# Optical_Compressor_V2.net
KiCad netlist of a schematic drawn in Altium Designer
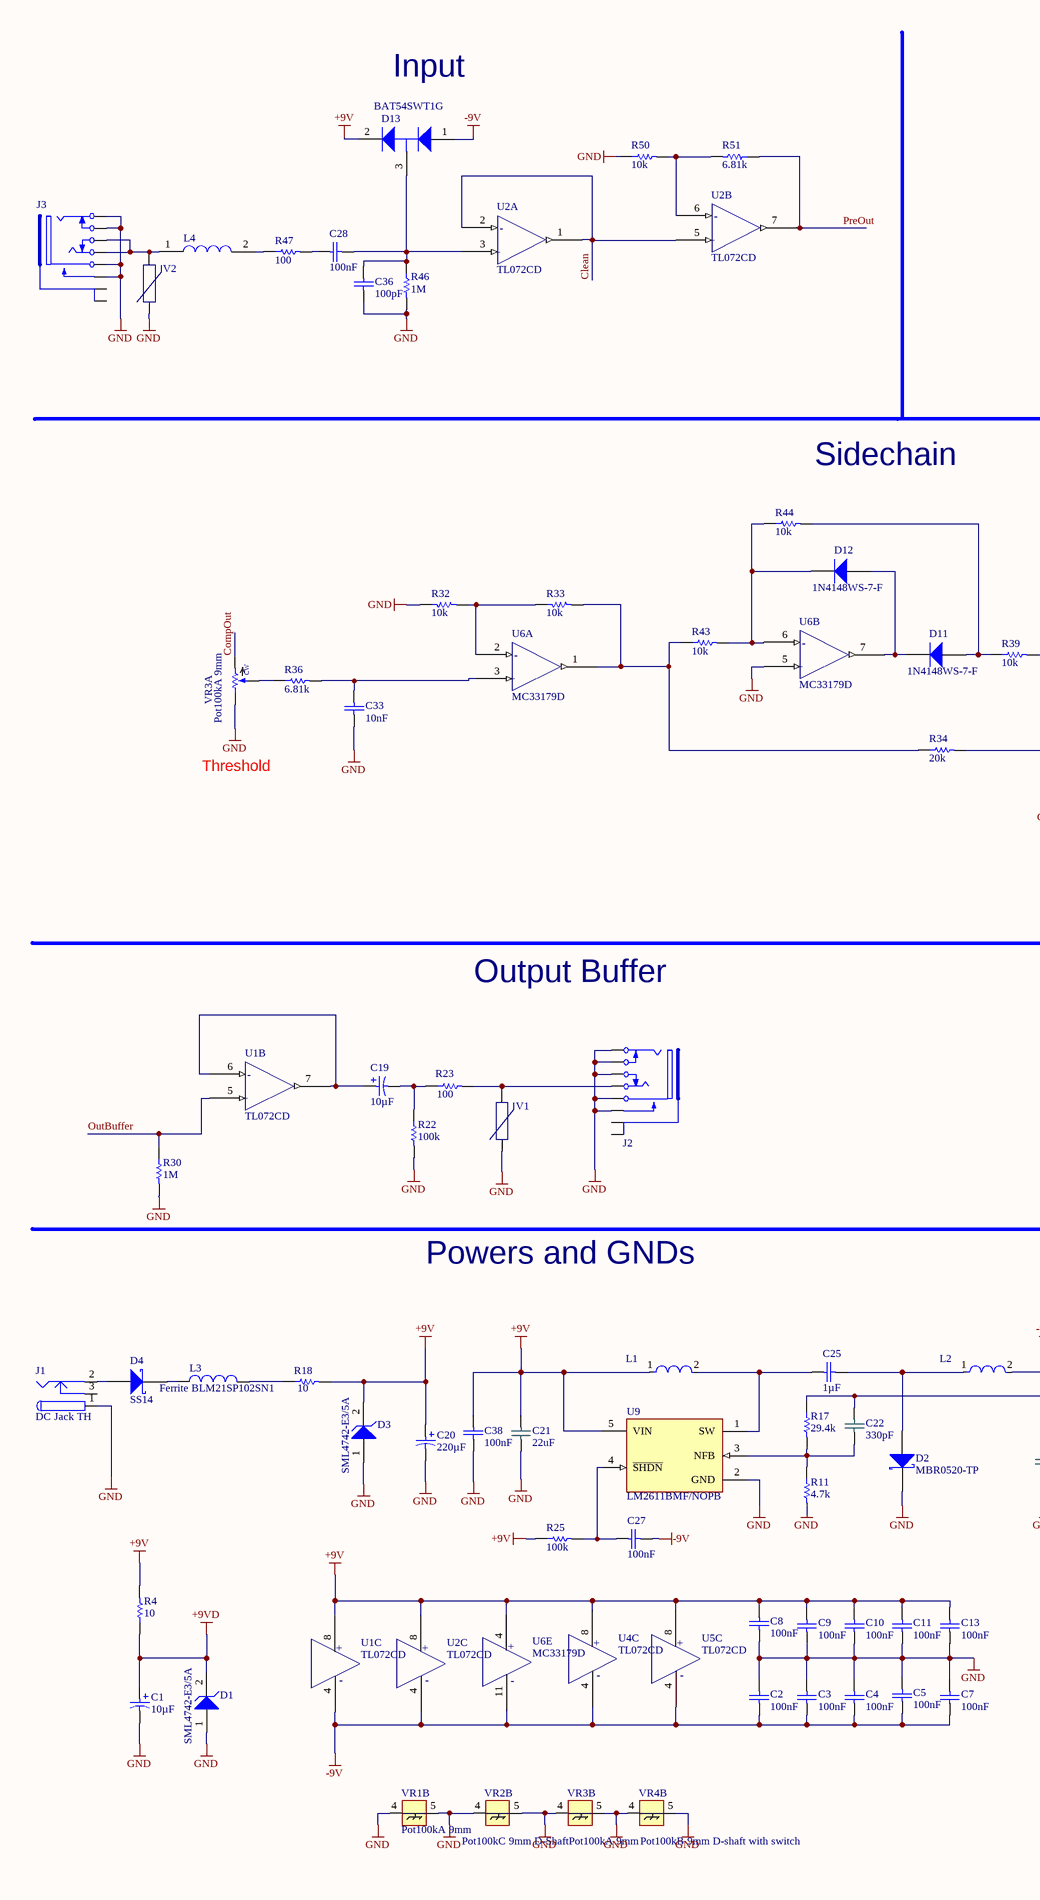
[diagram p0: Optical Compressor V2.SchDoc, left]
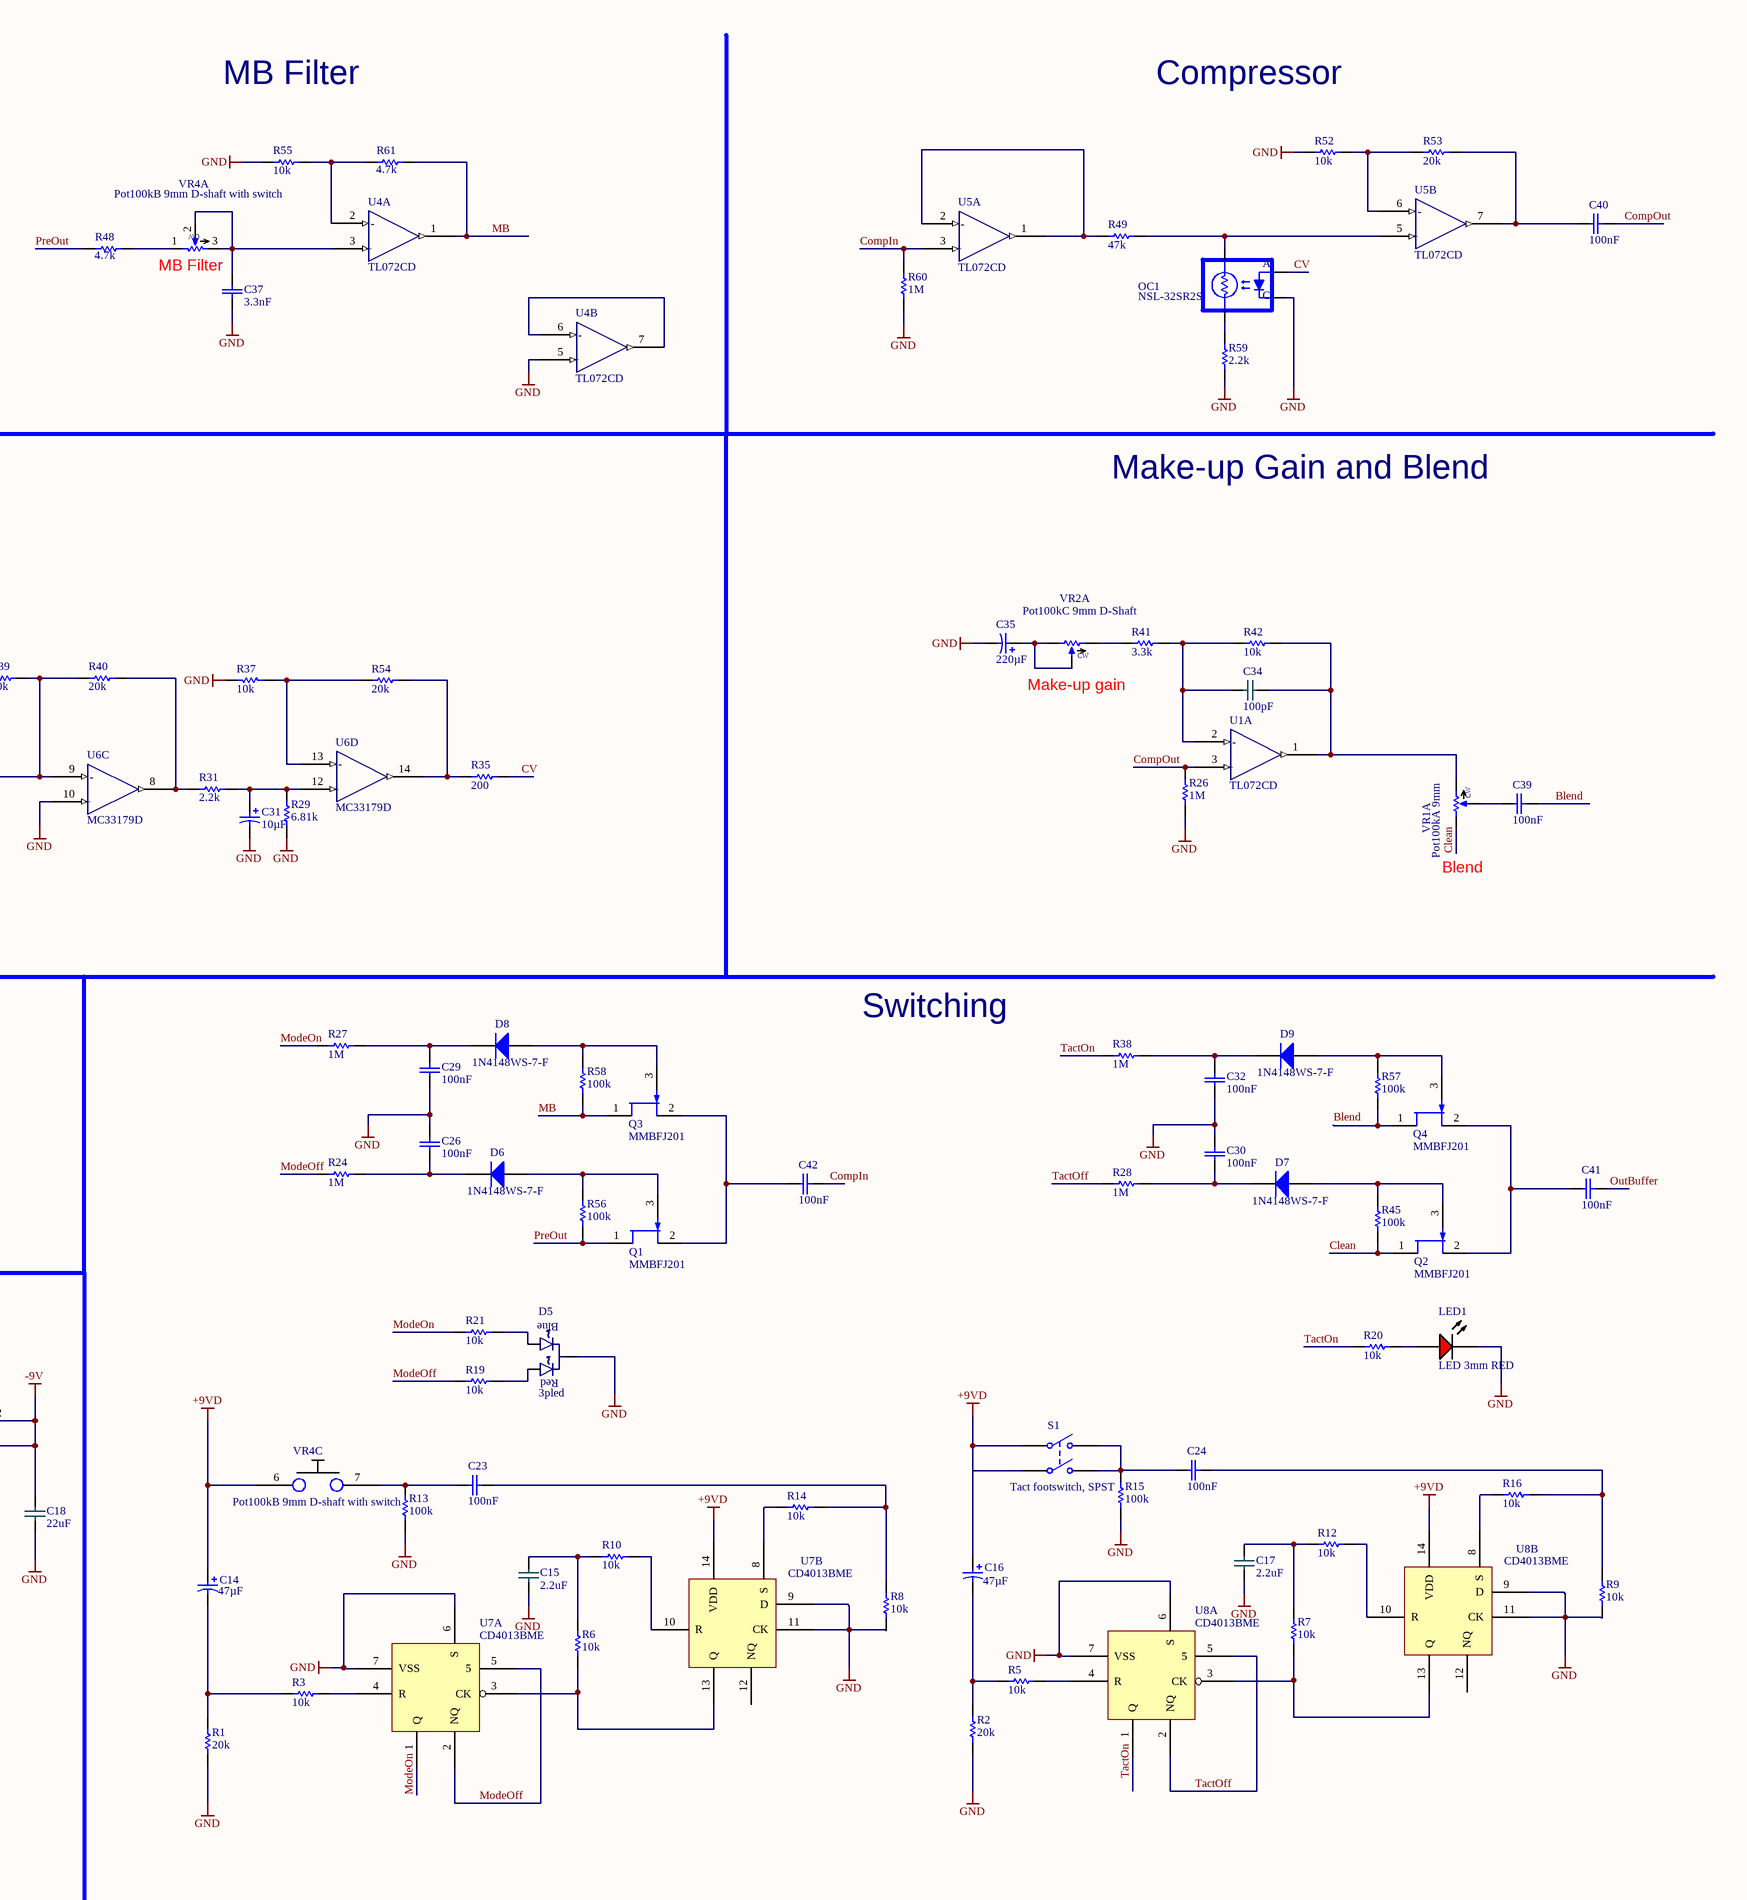
[diagram p1: Optical Compressor V2.SchDoc, right]

(export (version "E")
  (design (tool "Eeschema 10.0.6"))
  (components
    (comp (ref "C1")
      (value "Cap pol 10µF 35V")
      (footprint "E-CAP, SMT, diameter 5mm, height 5.4mm")
      (description "Cap Aluminum 10uF 35V ±20% (5x5.4mm) SMD 2000h 85°C")
      (fields (field (name "CAPACITANCE") "10µF"))
      (libsource (lib "Darkglass Electronics") (part "Capacitor Polarized"))
    )
    (comp (ref "C2")
      (value "Cap 100nF 0603 X7R")
      (footprint "0603-CAP")
      (description "Cap 100nF 0603 X7R 50V +-10%")
      (fields (field (name "CAPACITANCE") "100nF"))
      (libsource (lib "Darkglass Electronics") (part "Capacitor Non-polarized"))
    )
    (comp (ref "C3")
      (value "Cap 100nF 0603 X7R")
      (footprint "0603-CAP")
      (description "Cap 100nF 0603 X7R 50V +-10%")
      (fields (field (name "CAPACITANCE") "100nF"))
      (libsource (lib "Darkglass Electronics") (part "Capacitor Non-polarized"))
    )
    (comp (ref "C4")
      (value "Cap 100nF 0603 X7R")
      (footprint "0603-CAP")
      (description "Cap 100nF 0603 X7R 50V +-10%")
      (fields (field (name "CAPACITANCE") "100nF"))
      (libsource (lib "Darkglass Electronics") (part "Capacitor Non-polarized"))
    )
    (comp (ref "C5")
      (value "Cap 100nF 0603 X7R")
      (footprint "0603-CAP")
      (description "Cap 100nF 0603 X7R 50V +-10%")
      (fields (field (name "CAPACITANCE") "100nF"))
      (libsource (lib "Darkglass Electronics") (part "Capacitor Non-polarized"))
    )
    (comp (ref "C7")
      (value "Cap 100nF 0603 X7R")
      (footprint "0603-CAP")
      (description "Cap 100nF 0603 X7R 50V +-10%")
      (fields (field (name "CAPACITANCE") "100nF"))
      (libsource (lib "Darkglass Electronics") (part "Capacitor Non-polarized"))
    )
    (comp (ref "C8")
      (value "Cap 100nF 0603 X7R")
      (footprint "0603-CAP")
      (description "Cap 100nF 0603 X7R 50V +-10%")
      (fields (field (name "CAPACITANCE") "100nF"))
      (libsource (lib "Darkglass Electronics") (part "Capacitor Non-polarized"))
    )
    (comp (ref "C9")
      (value "Cap 100nF 0603 X7R")
      (footprint "0603-CAP")
      (description "Cap 100nF 0603 X7R 50V +-10%")
      (fields (field (name "CAPACITANCE") "100nF"))
      (libsource (lib "Darkglass Electronics") (part "Capacitor Non-polarized"))
    )
    (comp (ref "C10")
      (value "Cap 100nF 0603 X7R")
      (footprint "0603-CAP")
      (description "Cap 100nF 0603 X7R 50V +-10%")
      (fields (field (name "CAPACITANCE") "100nF"))
      (libsource (lib "Darkglass Electronics") (part "Capacitor Non-polarized"))
    )
    (comp (ref "C11")
      (value "Cap 100nF 0603 X7R")
      (footprint "0603-CAP")
      (description "Cap 100nF 0603 X7R 50V +-10%")
      (fields (field (name "CAPACITANCE") "100nF"))
      (libsource (lib "Darkglass Electronics") (part "Capacitor Non-polarized"))
    )
    (comp (ref "C13")
      (value "Cap 100nF 0603 X7R")
      (footprint "0603-CAP")
      (description "Cap 100nF 0603 X7R 50V +-10%")
      (fields (field (name "CAPACITANCE") "100nF"))
      (libsource (lib "Darkglass Electronics") (part "Capacitor Non-polarized"))
    )
    (comp (ref "C14")
      (value "Cap pol 47µF 16V")
      (footprint "E-CAP, SMT, diameter 6.3mm, height 5.4mm")
      (description "Cap Aluminum 47uF 16V ±20% (6.3x5.4mm) SMD 2000h 85°C")
      (fields (field (name "CAPACITANCE") "47µF"))
      (libsource (lib "Darkglass Electronics") (part "Capacitor Polarized"))
    )
    (comp (ref "C15")
      (value "Cap 0805 2.2uF")
      (footprint "0805-CAP")
      (description "2.2uF, 25V, X5R, 20%")
      (fields (field (name "TOLERANCE") "20%") (field (name "CAPACITANCE") "2.2uF"))
      (libsource (lib "Darkglass Electronics") (part "Capacitor NP"))
    )
    (comp (ref "C16")
      (value "Cap pol 47µF 16V")
      (footprint "E-CAP, SMT, diameter 6.3mm, height 5.4mm")
      (description "Cap Aluminum 47uF 16V ±20% (6.3x5.4mm) SMD 2000h 85°C")
      (fields (field (name "CAPACITANCE") "47µF"))
      (libsource (lib "Darkglass Electronics") (part "Capacitor Polarized"))
    )
    (comp (ref "C17")
      (value "Cap 0805 2.2uF")
      (footprint "0805-CAP")
      (description "2.2uF, 25V, X5R, 20%")
      (fields (field (name "TOLERANCE") "20%") (field (name "CAPACITANCE") "2.2uF"))
      (libsource (lib "Darkglass Electronics") (part "Capacitor NP"))
    )
    (comp (ref "C18")
      (value "22uF")
      (footprint "0805-CAP")
      (description "22uF, 16V, X5R, 20%")
      (fields
        (field (name "TOLERANCE") "20%")
        (field (name "VOLTAGE") "16V")
        (field (name "PUBLISHER") "Altium Limited")
      )
      (libsource (lib "Darkglass Electronics") (part "=Capacitance"))
    )
    (comp (ref "C19")
      (value "Cap pol 10µF 35V")
      (footprint "E-CAP, SMT, diameter 5mm, height 5.4mm")
      (description "Cap Aluminum 10uF 35V ±20% (5x5.4mm) SMD 2000h 85°C")
      (fields (field (name "CAPACITANCE") "10µF"))
      (libsource (lib "Darkglass Electronics") (part "Capacitor Polarized"))
    )
    (comp (ref "C20")
      (value "Cap pol 220µF 16V")
      (footprint "E-CAP, SMT, diameter 6.3mm, height 7.7mm")
      (description "Cap Aluminum 220uF 16V ±20% (6.3x7.7mm) SMD 2000h 85°C")
      (fields (field (name "CAPACITANCE") "220µF"))
      (libsource (lib "Darkglass Electronics") (part "Capacitor Polarized"))
    )
    (comp (ref "C21")
      (value "22uF")
      (footprint "0805-CAP")
      (description "22uF, 16V, X5R, 20%")
      (fields
        (field (name "TOLERANCE") "20%")
        (field (name "VOLTAGE") "16V")
        (field (name "PUBLISHER") "Altium Limited")
      )
      (libsource (lib "Darkglass Electronics") (part "=Capacitance"))
    )
    (comp (ref "C22")
      (value "330pF")
      (footprint "0603-CAP")
      (description "330pF,  5%,  50V,  C0G")
      (fields (field (name "TOLERANCE") "5%") (field (name "VOLTAGE") "50V"))
      (libsource (lib "Darkglass Electronics") (part "Capacitor NP"))
    )
    (comp (ref "C23")
      (value "Cap 100nF 0603 X7R")
      (footprint "0603-CAP")
      (description "Cap 100nF 0603 X7R 50V +-10%")
      (fields (field (name "CAPACITANCE") "100nF"))
      (libsource (lib "Darkglass Electronics") (part "Capacitor Non-polarized"))
    )
    (comp (ref "C24")
      (value "Cap 100nF 0603 X7R")
      (footprint "0603-CAP")
      (description "Cap 100nF 0603 X7R 50V +-10%")
      (fields (field (name "CAPACITANCE") "100nF"))
      (libsource (lib "Darkglass Electronics") (part "Capacitor Non-polarized"))
    )
    (comp (ref "C25")
      (value "Cap 1µF 0805 X7R")
      (footprint "0805-CAP")
      (description "Cap 1µF 0805 X7R 50V +-10%")
      (fields (field (name "CAPACITANCE") "1µF"))
      (libsource (lib "Darkglass Electronics") (part "Capacitor Non-polarized"))
    )
    (comp (ref "C26")
      (value "Cap 100nF 0603 X7R")
      (footprint "0603-CAP")
      (description "Cap 100nF 0603 X7R 50V +-10%")
      (fields (field (name "CAPACITANCE") "100nF"))
      (libsource (lib "Darkglass Electronics") (part "Capacitor Non-polarized"))
    )
    (comp (ref "C27")
      (value "Cap 100nF 0603 X7R")
      (footprint "0603-CAP")
      (description "Cap 100nF 0603 X7R 50V +-10%")
      (fields (field (name "CAPACITANCE") "100nF"))
      (libsource (lib "Darkglass Electronics") (part "Capacitor Non-polarized"))
    )
    (comp (ref "C28")
      (value "Cap 100nF 1206 C0G")
      (footprint "1206-CAP")
      (description "Cap 100nF 1206 C0G 50V +-5%")
      (fields (field (name "CAPACITANCE") "100nF"))
      (libsource (lib "Darkglass Electronics") (part "Capacitor Non-polarized"))
    )
    (comp (ref "C29")
      (value "Cap 100nF 0603 X7R")
      (footprint "0603-CAP")
      (description "Cap 100nF 0603 X7R 50V +-10%")
      (fields (field (name "CAPACITANCE") "100nF"))
      (libsource (lib "Darkglass Electronics") (part "Capacitor Non-polarized"))
    )
    (comp (ref "C30")
      (value "Cap 100nF 0603 X7R")
      (footprint "0603-CAP")
      (description "Cap 100nF 0603 X7R 50V +-10%")
      (fields (field (name "CAPACITANCE") "100nF"))
      (libsource (lib "Darkglass Electronics") (part "Capacitor Non-polarized"))
    )
    (comp (ref "C31")
      (value "Cap pol 10µF 35V")
      (footprint "E-CAP, SMT, diameter 5mm, height 5.4mm")
      (description "Cap Aluminum 10uF 35V ±20% (5x5.4mm) SMD 2000h 85°C")
      (fields (field (name "CAPACITANCE") "10µF"))
      (libsource (lib "Darkglass Electronics") (part "Capacitor Polarized"))
    )
    (comp (ref "C32")
      (value "Cap 100nF 0603 X7R")
      (footprint "0603-CAP")
      (description "Cap 100nF 0603 X7R 50V +-10%")
      (fields (field (name "CAPACITANCE") "100nF"))
      (libsource (lib "Darkglass Electronics") (part "Capacitor Non-polarized"))
    )
    (comp (ref "C33")
      (value "Cap 10nF 0603 C0G")
      (footprint "0603-CAP")
      (description "Cap 10nF 0603 C0G 50V +-5%")
      (fields (field (name "CAPACITANCE") "10nF"))
      (libsource (lib "Darkglass Electronics") (part "Capacitor Non-polarized"))
    )
    (comp (ref "C34")
      (value "Cap 0603 100pF")
      (footprint "0603-CAP")
      (description "100pF, 50V, COG,  5%")
      (fields
        (field (name "CAPACITANCE") "100pF")
        (field (name "TOLERANCE") "5%")
        (field (name "PUBLISHER") "Altium Limited")
      )
      (libsource (lib "Darkglass Electronics") (part "Capacitor NP"))
    )
    (comp (ref "C35")
      (value "Cap pol 220µF 16V")
      (footprint "E-CAP, SMT, diameter 6.3mm, height 7.7mm")
      (description "Cap Aluminum 220uF 16V ±20% (6.3x7.7mm) SMD 2000h 85°C")
      (fields (field (name "CAPACITANCE") "220µF"))
      (libsource (lib "Darkglass Electronics") (part "Capacitor Polarized"))
    )
    (comp (ref "C36")
      (value "Cap 100pF 0603 C0G")
      (footprint "0603-CAP")
      (description "Cap 100pF 0603 C0G 50V +-5%")
      (fields (field (name "CAPACITANCE") "100pF"))
      (libsource (lib "Darkglass Electronics") (part "Capacitor Non-polarized"))
    )
    (comp (ref "C37")
      (value "Cap 3.3nF 0603 C0G")
      (footprint "0603-CAP")
      (description "Cap 3.3nF 0603 C0G 50V +-5%")
      (fields (field (name "CAPACITANCE") "3.3nF"))
      (libsource (lib "Darkglass Electronics") (part "Capacitor Non-polarized"))
    )
    (comp (ref "C38")
      (value "Cap 100nF 0603 X7R")
      (footprint "0603-CAP")
      (description "Cap 100nF 0603 X7R 50V +-10%")
      (fields (field (name "CAPACITANCE") "100nF"))
      (libsource (lib "Darkglass Electronics") (part "Capacitor Non-polarized"))
    )
    (comp (ref "C39")
      (value "Cap 100nF 1206 C0G")
      (footprint "1206-CAP")
      (description "Cap 100nF 1206 C0G 50V +-5%")
      (fields (field (name "CAPACITANCE") "100nF"))
      (libsource (lib "Darkglass Electronics") (part "Capacitor Non-polarized"))
    )
    (comp (ref "C40")
      (value "Cap 100nF 1206 C0G")
      (footprint "1206-CAP")
      (description "Cap 100nF 1206 C0G 50V +-5%")
      (fields (field (name "CAPACITANCE") "100nF"))
      (libsource (lib "Darkglass Electronics") (part "Capacitor Non-polarized"))
    )
    (comp (ref "C41")
      (value "Cap 100nF 1206 C0G")
      (footprint "1206-CAP")
      (description "Cap 100nF 1206 C0G 50V +-5%")
      (fields (field (name "CAPACITANCE") "100nF"))
      (libsource (lib "Darkglass Electronics") (part "Capacitor Non-polarized"))
    )
    (comp (ref "C42")
      (value "Cap 100nF 1206 C0G")
      (footprint "1206-CAP")
      (description "Cap 100nF 1206 C0G 50V +-5%")
      (fields (field (name "CAPACITANCE") "100nF"))
      (libsource (lib "Darkglass Electronics") (part "Capacitor Non-polarized"))
    )
    (comp (ref "D1")
      (value "SML4742-E3/5A")
      (footprint "DO-214AC")
      (description "12V Zener")
      (fields (field (name "TOLERANCE") "10%") (field (name "MANUFACTURER") "Vishay Semiconductors"))
      (libsource (lib "") (part "Symbol_3"))
    )
    (comp (ref "D2")
      (value "MBR0520-TP")
      (footprint "SODFL370X135-2N")
      (description "Rectifier Diode, Schottky, 1 Phase, 1 Element, 0.5A, 20V V(RRM), Silicon")
      (libsource (lib "Darkglass Electronics") (part "SS14"))
    )
    (comp (ref "D3")
      (value "SML4742-E3/5A")
      (footprint "DO-214AC")
      (description "12V Zener")
      (fields (field (name "TOLERANCE") "10%") (field (name "MANUFACTURER") "Vishay Semiconductors"))
      (libsource (lib "") (part "Symbol_3"))
    )
    (comp (ref "D4")
      (value "SS14")
      (footprint "SS14")
      (description "ON SEMICONDUCTOR - SS14 - DIODE, SCHOTTKY, 1A, 40V, DO-214AC-2")
      (fields (field (name "MANUFACTURER") "ON Semiconductor / Fairchild") (field (name "VOLTAGE") "40V"))
      (libsource (lib "") (part "SS14_1"))
    )
    (comp (ref "D5")
      (value "3pled")
      (footprint "LED DUAL REDBLUE")
      (description "3pin led red/blue")
      (fields
        (field (name "MANUFACTURER PART NUMBER") "OSRBMC3131A")
        (field (name "MANUFACTURER") "OptoSupply")
      )
      (libsource (lib "Darkglass Electronics") (part "3pled"))
    )
    (comp (ref "D6")
      (value "1N4148WS-7-F")
      (footprint "1N4148WS-7-F")
      (description "Fast Switching Diode, 75 V, 0.3 A, -65 to 150 degC, 2-Pin SOD323, RoHS, Tape and Reel")
      (fields
        (field (name "VOLTAGE") "75V")
        (field (name "MANUFACTURER") "Pericom")
        (field (name "AVAILABLE PREVIEW IMAGES") "2D")
      )
      (libsource (lib "") (part "Symbol_2"))
    )
    (comp (ref "D7")
      (value "1N4148WS-7-F")
      (footprint "1N4148WS-7-F")
      (description "Fast Switching Diode, 75 V, 0.3 A, -65 to 150 degC, 2-Pin SOD323, RoHS, Tape and Reel")
      (fields
        (field (name "VOLTAGE") "75V")
        (field (name "MANUFACTURER") "Pericom")
        (field (name "AVAILABLE PREVIEW IMAGES") "2D")
      )
      (libsource (lib "") (part "Symbol_2"))
    )
    (comp (ref "D8")
      (value "1N4148WS-7-F")
      (footprint "1N4148WS-7-F")
      (description "Fast Switching Diode, 75 V, 0.3 A, -65 to 150 degC, 2-Pin SOD323, RoHS, Tape and Reel")
      (fields
        (field (name "VOLTAGE") "75V")
        (field (name "MANUFACTURER") "Pericom")
        (field (name "AVAILABLE PREVIEW IMAGES") "2D")
      )
      (libsource (lib "") (part "Symbol_2"))
    )
    (comp (ref "D9")
      (value "1N4148WS-7-F")
      (footprint "1N4148WS-7-F")
      (description "Fast Switching Diode, 75 V, 0.3 A, -65 to 150 degC, 2-Pin SOD323, RoHS, Tape and Reel")
      (fields
        (field (name "VOLTAGE") "75V")
        (field (name "MANUFACTURER") "Pericom")
        (field (name "AVAILABLE PREVIEW IMAGES") "2D")
      )
      (libsource (lib "") (part "Symbol_2"))
    )
    (comp (ref "D11")
      (value "1N4148WS-7-F")
      (footprint "1N4148WS-7-F")
      (description "Fast Switching Diode, 75 V, 0.3 A, -65 to 150 degC, 2-Pin SOD323, RoHS, Tape and Reel")
      (fields
        (field (name "VOLTAGE") "75V")
        (field (name "MANUFACTURER") "Pericom")
        (field (name "AVAILABLE PREVIEW IMAGES") "2D")
      )
      (libsource (lib "") (part "Symbol_2"))
    )
    (comp (ref "D12")
      (value "1N4148WS-7-F")
      (footprint "1N4148WS-7-F")
      (description "Fast Switching Diode, 75 V, 0.3 A, -65 to 150 degC, 2-Pin SOD323, RoHS, Tape and Reel")
      (fields
        (field (name "VOLTAGE") "75V")
        (field (name "MANUFACTURER") "Pericom")
        (field (name "AVAILABLE PREVIEW IMAGES") "2D")
      )
      (libsource (lib "") (part "Symbol_2"))
    )
    (comp (ref "D13")
      (value "BAT54SWT1G")
      (footprint "ONSC-SOT-323-3-419-04_V")
      (description "Rectifier Diode, Schottky, 2 Element, 0.2A, 30V V(RRM), Silicon")
      (libsource (lib "Darkglass Electronics") (part "ONSC-D-A1K2C3-3"))
    )
    (comp (ref "J1")
      (value "DC Jack TH")
      (footprint "DC_Jack")
      (description "Low Voltage Power Supply Connector")
      (fields (field (name "DARKGLASS PART") "D00-0019"))
      (libsource (lib "") (part "Symbol_8"))
    )
    (comp (ref "J2")
      (value "Neutrik TRS Jack with metal nut")
      (footprint "Neutrik Jack with Cliff EMI screen")
      (fields (field (name "DARKGLASS PART") "D00-0011"))
      (libsource (lib "Darkglass Electronics") (part "Neutrik TRS Jack with metal nut"))
    )
    (comp (ref "J3")
      (value "Neutrik TRS Jack with metal nut")
      (footprint "Neutrik Jack with Cliff EMI screen")
      (fields (field (name "DARKGLASS PART") "D00-0011"))
      (libsource (lib "Darkglass Electronics") (part "Neutrik TRS Jack with metal nut"))
    )
    (comp (ref "L1")
      (value "CR32NP-100KC")
      (footprint "INDC3340X27N")
      (description "General Purpose Inductor, 10uH, 10%, 1 Element, Ferrite-Core, SMD, 1514")
      (fields (field (name "TOLERANCE") "10%"))
      (libsource (lib "Darkglass Electronics") (part "725321dda6339637d4d059423bc1c3c"))
    )
    (comp (ref "L2")
      (value "CR32NP-100KC")
      (footprint "INDC3340X27N")
      (description "General Purpose Inductor, 10uH, 10%, 1 Element, Ferrite-Core, SMD, 1514")
      (fields (field (name "TOLERANCE") "10%"))
      (libsource (lib "Darkglass Electronics") (part "725321dda6339637d4d059423bc1c3c"))
    )
    (comp (ref "L3")
      (value "Ferrite BLM21SP102SN1")
      (footprint "0805-IND")
      (description "Ferrite Beads Multi-Layer High Current 1KOhm 25% 100MHz 1.6A 0.12Ohm DCR")
      (fields
        (field (name "MANUFACTURER PART NUMBER") "BLM21SP102SN1D")
        (field (name "MANUFACTURER") "Murata")
        (field (name "SOURCE") "jimi.SchLib")
      )
      (libsource (lib "Darkglass Electronics") (part "ferrite 1k 0805"))
    )
    (comp (ref "L4")
      (value "MAF1005GAD352A")
      (footprint "0402 COMPONENT")
      (description "FERRITE BEAD, AUDIO, 500 OHM 0402 Low THD+N")
      (libsource (lib "Darkglass Electronics") (part "Audio 500R 0402"))
    )
    (comp (ref "LED1")
      (value "LED 3mm RED")
      (footprint "KING-WP710A10QBCD_V")
      (description "THT LED round mono-color waterclear, WL-TMRW , RED")
      (fields
        (field (name "DARKGLASS PART") "D00-0042")
        (field (name "MANUFACTURER") "Wuerth Elektronik")
        (field (name "AVAILABLE PREVIEW IMAGES") "2D")
      )
      (libsource (lib "Darkglass Electronics") (part "LED 3mm RED"))
    )
    (comp (ref "OC1")
      (value "NSL-32SR2S")
      (footprint "NSL")
      (description "Optoisolator Photocell Optocoupler 1 Channel")
      (fields (field (name "MF") "Advanced Photonix"))
      (libsource (lib "SnapEDAsch") (part "NSL-32SR2S"))
    )
    (comp (ref "Q1")
      (value "MMBFJ201")
      (footprint "MMBFJ201")
      (description "JFET N-CH 40V 350MW SOT23")
      (fields
        (field (name "MOUSER PART") "512-MMBFJ201")
        (field (name "MANUFACTURER") "ON Semiconductor / Fairchild")
      )
      (libsource (lib "") (part "Symbol_1"))
    )
    (comp (ref "Q2")
      (value "MMBFJ201")
      (footprint "MMBFJ201")
      (description "JFET N-CH 40V 350MW SOT23")
      (fields
        (field (name "MOUSER PART") "512-MMBFJ201")
        (field (name "MANUFACTURER") "ON Semiconductor / Fairchild")
      )
      (libsource (lib "") (part "Symbol_1"))
    )
    (comp (ref "Q3")
      (value "MMBFJ201")
      (footprint "MMBFJ201")
      (description "JFET N-CH 40V 350MW SOT23")
      (fields
        (field (name "MOUSER PART") "512-MMBFJ201")
        (field (name "MANUFACTURER") "ON Semiconductor / Fairchild")
      )
      (libsource (lib "") (part "Symbol_1"))
    )
    (comp (ref "Q4")
      (value "MMBFJ201")
      (footprint "MMBFJ201")
      (description "JFET N-CH 40V 350MW SOT23")
      (fields
        (field (name "MOUSER PART") "512-MMBFJ201")
        (field (name "MANUFACTURER") "ON Semiconductor / Fairchild")
      )
      (libsource (lib "") (part "Symbol_1"))
    )
    (comp (ref "R1")
      (value "Res 20k 1% 0603")
      (footprint "0603-RES")
      (description "Resistor 20k +-1% 0603 Thin film 0.1W +-50ppm/°C")
      (fields (field (name "RESISTANCE") "20k") (field (name "POWER") "100mW"))
      (libsource (lib "Darkglass Electronics") (part "Resistor"))
    )
    (comp (ref "R2")
      (value "Res 20k 1% 0603")
      (footprint "0603-RES")
      (description "Resistor 20k +-1% 0603 Thin film 0.1W +-50ppm/°C")
      (fields (field (name "RESISTANCE") "20k") (field (name "POWER") "100mW"))
      (libsource (lib "Darkglass Electronics") (part "Resistor"))
    )
    (comp (ref "R3")
      (value "Res 10k 1% 0603")
      (footprint "0603-RES")
      (description "Resistor 10k +-1% 0603 Thick film 0.1W +- 100ppm/°C")
      (fields (field (name "RESISTANCE") "10k") (field (name "POWER") "100mW"))
      (libsource (lib "Darkglass Electronics") (part "Resistor"))
    )
    (comp (ref "R4")
      (value "Res 10R 5% 0805")
      (footprint "0805-RES")
      (description "Resistor 10R +-5% 0805 Thick film 0.125W +-200ppm/°C")
      (fields (field (name "POWER") "125mW") (field (name "RESISTANCE") "10"))
      (libsource (lib "Darkglass Electronics") (part "Resistor"))
    )
    (comp (ref "R5")
      (value "Res 10k 1% 0603")
      (footprint "0603-RES")
      (description "Resistor 10k +-1% 0603 Thick film 0.1W +- 100ppm/°C")
      (fields (field (name "RESISTANCE") "10k") (field (name "POWER") "100mW"))
      (libsource (lib "Darkglass Electronics") (part "Resistor"))
    )
    (comp (ref "R6")
      (value "Res 10k 1% 0603")
      (footprint "0603-RES")
      (description "Resistor 10k +-1% 0603 Thick film 0.1W +- 100ppm/°C")
      (fields (field (name "RESISTANCE") "10k") (field (name "POWER") "100mW"))
      (libsource (lib "Darkglass Electronics") (part "Resistor"))
    )
    (comp (ref "R7")
      (value "Res 10k 1% 0603")
      (footprint "0603-RES")
      (description "Resistor 10k +-1% 0603 Thick film 0.1W +- 100ppm/°C")
      (fields (field (name "RESISTANCE") "10k") (field (name "POWER") "100mW"))
      (libsource (lib "Darkglass Electronics") (part "Resistor"))
    )
    (comp (ref "R8")
      (value "Res 10k 1% 0603")
      (footprint "0603-RES")
      (description "Resistor 10k +-1% 0603 Thick film 0.1W +- 100ppm/°C")
      (fields (field (name "RESISTANCE") "10k") (field (name "POWER") "100mW"))
      (libsource (lib "Darkglass Electronics") (part "Resistor"))
    )
    (comp (ref "R9")
      (value "Res 10k 1% 0603")
      (footprint "0603-RES")
      (description "Resistor 10k +-1% 0603 Thick film 0.1W +- 100ppm/°C")
      (fields (field (name "RESISTANCE") "10k") (field (name "POWER") "100mW"))
      (libsource (lib "Darkglass Electronics") (part "Resistor"))
    )
    (comp (ref "R10")
      (value "Res 10k 1% 0603")
      (footprint "0603-RES")
      (description "Resistor 10k +-1% 0603 Thick film 0.1W +- 100ppm/°C")
      (fields (field (name "RESISTANCE") "10k") (field (name "POWER") "100mW"))
      (libsource (lib "Darkglass Electronics") (part "Resistor"))
    )
    (comp (ref "R11")
      (value "Res 4.7k 1% 0603")
      (footprint "0603-RES")
      (description "Resistor 4.7k +-1% 0603 Thin film 0.1W +-50ppm/°C")
      (fields (field (name "POWER") "100mW") (field (name "RESISTANCE") "4.7k"))
      (libsource (lib "Darkglass Electronics") (part "Resistor"))
    )
    (comp (ref "R12")
      (value "Res 10k 1% 0603")
      (footprint "0603-RES")
      (description "Resistor 10k +-1% 0603 Thick film 0.1W +- 100ppm/°C")
      (fields (field (name "RESISTANCE") "10k") (field (name "POWER") "100mW"))
      (libsource (lib "Darkglass Electronics") (part "Resistor"))
    )
    (comp (ref "R13")
      (value "Res 100k 1% 0603")
      (footprint "0603-RES")
      (description "Resistor 100k +-1% 0603 Thin film 0.1W +-50ppm/°C")
      (fields (field (name "POWER") "100mW") (field (name "RESISTANCE") "100k"))
      (libsource (lib "Darkglass Electronics") (part "Resistor"))
    )
    (comp (ref "R14")
      (value "Res 10k 1% 0603")
      (footprint "0603-RES")
      (description "Resistor 10k +-1% 0603 Thick film 0.1W +- 100ppm/°C")
      (fields (field (name "RESISTANCE") "10k") (field (name "POWER") "100mW"))
      (libsource (lib "Darkglass Electronics") (part "Resistor"))
    )
    (comp (ref "R15")
      (value "Res 100k 1% 0603")
      (footprint "0603-RES")
      (description "Resistor 100k +-1% 0603 Thin film 0.1W +-50ppm/°C")
      (fields (field (name "POWER") "100mW") (field (name "RESISTANCE") "100k"))
      (libsource (lib "Darkglass Electronics") (part "Resistor"))
    )
    (comp (ref "R16")
      (value "Res 10k 1% 0603")
      (footprint "0603-RES")
      (description "Resistor 10k +-1% 0603 Thick film 0.1W +- 100ppm/°C")
      (fields (field (name "RESISTANCE") "10k") (field (name "POWER") "100mW"))
      (libsource (lib "Darkglass Electronics") (part "Resistor"))
    )
    (comp (ref "R17")
      (value "Res 29.4k 1% 0805")
      (footprint "0805-RES")
      (description "Resistor 29.4k +-1% 0805 Thick film 0.125W +- 100ppm/°C")
      (fields (field (name "RESISTANCE") "29.4k") (field (name "POWER") "125mW"))
      (libsource (lib "Darkglass Electronics") (part "Resistor"))
    )
    (comp (ref "R18")
      (value "Res 10R 5% 0805")
      (footprint "0805-RES")
      (description "Resistor 10R +-5% 0805 Thick film 0.125W +-200ppm/°C")
      (fields (field (name "POWER") "125mW") (field (name "RESISTANCE") "10"))
      (libsource (lib "Darkglass Electronics") (part "Resistor"))
    )
    (comp (ref "R19")
      (value "Res 10k 1% 0603")
      (footprint "0603-RES")
      (description "Resistor 10k +-1% 0603 Thick film 0.1W +- 100ppm/°C")
      (fields (field (name "RESISTANCE") "10k") (field (name "POWER") "100mW"))
      (libsource (lib "Darkglass Electronics") (part "Resistor"))
    )
    (comp (ref "R20")
      (value "Res 10k 1% 0603")
      (footprint "0603-RES")
      (description "Resistor 10k +-1% 0603 Thick film 0.1W +- 100ppm/°C")
      (fields (field (name "RESISTANCE") "10k") (field (name "POWER") "100mW"))
      (libsource (lib "Darkglass Electronics") (part "Resistor"))
    )
    (comp (ref "R21")
      (value "Res 10k 1% 0603")
      (footprint "0603-RES")
      (description "Resistor 10k +-1% 0603 Thick film 0.1W +- 100ppm/°C")
      (fields (field (name "RESISTANCE") "10k") (field (name "POWER") "100mW"))
      (libsource (lib "Darkglass Electronics") (part "Resistor"))
    )
    (comp (ref "R22")
      (value "Res 100k 1% 0603")
      (footprint "0603-RES")
      (description "Resistor 100k +-1% 0603 Thin film 0.1W +-50ppm/°C")
      (fields (field (name "POWER") "100mW") (field (name "RESISTANCE") "100k"))
      (libsource (lib "Darkglass Electronics") (part "Resistor"))
    )
    (comp (ref "R23")
      (value "Res 100R 1% 0805")
      (footprint "0805-RES")
      (description "Resistor 100R +-1% 0805 Thin film 0.125W +-50ppm/°C")
      (fields (field (name "POWER") "125mW") (field (name "RESISTANCE") "100"))
      (libsource (lib "Darkglass Electronics") (part "Resistor"))
    )
    (comp (ref "R24")
      (value "Res 1M 1% 0603")
      (footprint "0603-RES")
      (description "Resistor 1M +-1% 0603 Thin film 0.1W +-50ppm/°C")
      (fields (field (name "POWER") "100mW") (field (name "RESISTANCE") "1M"))
      (libsource (lib "Darkglass Electronics") (part "Resistor"))
    )
    (comp (ref "R25")
      (value "Res 100k 1% 0603")
      (footprint "0603-RES")
      (description "Resistor 100k +-1% 0603 Thin film 0.1W +-50ppm/°C")
      (fields (field (name "POWER") "100mW") (field (name "RESISTANCE") "100k"))
      (libsource (lib "Darkglass Electronics") (part "Resistor"))
    )
    (comp (ref "R26")
      (value "Res 1M 1% 0603")
      (footprint "0603-RES")
      (description "Resistor 1M +-1% 0603 Thin film 0.1W +-50ppm/°C")
      (fields (field (name "POWER") "100mW") (field (name "RESISTANCE") "1M"))
      (libsource (lib "Darkglass Electronics") (part "Resistor"))
    )
    (comp (ref "R27")
      (value "Res 1M 1% 0603")
      (footprint "0603-RES")
      (description "Resistor 1M +-1% 0603 Thin film 0.1W +-50ppm/°C")
      (fields (field (name "POWER") "100mW") (field (name "RESISTANCE") "1M"))
      (libsource (lib "Darkglass Electronics") (part "Resistor"))
    )
    (comp (ref "R28")
      (value "Res 1M 1% 0603")
      (footprint "0603-RES")
      (description "Resistor 1M +-1% 0603 Thin film 0.1W +-50ppm/°C")
      (fields (field (name "POWER") "100mW") (field (name "RESISTANCE") "1M"))
      (libsource (lib "Darkglass Electronics") (part "Resistor"))
    )
    (comp (ref "R29")
      (value "Res 6.81k 1% 0603")
      (footprint "0603-RES")
      (description "Resistor 6.81k +-1% 0603 Thin film 0.1W +-50ppm/°C")
      (fields (field (name "POWER") "100mW") (field (name "RESISTANCE") "6.81k"))
      (libsource (lib "Darkglass Electronics") (part "Resistor"))
    )
    (comp (ref "R30")
      (value "Res 1M 1% 0603")
      (footprint "0603-RES")
      (description "Resistor 1M +-1% 0603 Thin film 0.1W +-50ppm/°C")
      (fields (field (name "POWER") "100mW") (field (name "RESISTANCE") "1M"))
      (libsource (lib "Darkglass Electronics") (part "Resistor"))
    )
    (comp (ref "R31")
      (value "Res 2.2k 1% 0603")
      (footprint "0603-RES")
      (description "Resistor 2.2k +-1% 0603 Thin film 0.1W +-50ppm/°C")
      (fields (field (name "POWER") "100mW") (field (name "RESISTANCE") "2.2k"))
      (libsource (lib "Darkglass Electronics") (part "Resistor"))
    )
    (comp (ref "R32")
      (value "Res 10k 1% 0603")
      (footprint "0603-RES")
      (description "Resistor 10k +-1% 0603 Thick film 0.1W +- 100ppm/°C")
      (fields (field (name "RESISTANCE") "10k") (field (name "POWER") "100mW"))
      (libsource (lib "Darkglass Electronics") (part "Resistor"))
    )
    (comp (ref "R33")
      (value "Res 10k 1% 0603")
      (footprint "0603-RES")
      (description "Resistor 10k +-1% 0603 Thick film 0.1W +- 100ppm/°C")
      (fields (field (name "RESISTANCE") "10k") (field (name "POWER") "100mW"))
      (libsource (lib "Darkglass Electronics") (part "Resistor"))
    )
    (comp (ref "R34")
      (value "Res 20k 1% 0603")
      (footprint "0603-RES")
      (description "Resistor 20k +-1% 0603 Thin film 0.1W +-50ppm/°C")
      (fields (field (name "RESISTANCE") "20k") (field (name "POWER") "100mW"))
      (libsource (lib "Darkglass Electronics") (part "Resistor"))
    )
    (comp (ref "R35")
      (value "Res 200R 1% 0805")
      (footprint "0805-RES")
      (description "Resistor 200R +-1% 0805 Thin film 0.125W +-50ppm/°C")
      (fields (field (name "POWER") "125mW") (field (name "RESISTANCE") "200"))
      (libsource (lib "Darkglass Electronics") (part "Resistor"))
    )
    (comp (ref "R36")
      (value "Res 6.81k 1% 0603")
      (footprint "0603-RES")
      (description "Resistor 6.81k +-1% 0603 Thin film 0.1W +-50ppm/°C")
      (fields (field (name "POWER") "100mW") (field (name "RESISTANCE") "6.81k"))
      (libsource (lib "Darkglass Electronics") (part "Resistor"))
    )
    (comp (ref "R37")
      (value "Res 10k 1% 0603")
      (footprint "0603-RES")
      (description "Resistor 10k +-1% 0603 Thick film 0.1W +- 100ppm/°C")
      (fields (field (name "RESISTANCE") "10k") (field (name "POWER") "100mW"))
      (libsource (lib "Darkglass Electronics") (part "Resistor"))
    )
    (comp (ref "R38")
      (value "Res 1M 1% 0603")
      (footprint "0603-RES")
      (description "Resistor 1M +-1% 0603 Thin film 0.1W +-50ppm/°C")
      (fields (field (name "POWER") "100mW") (field (name "RESISTANCE") "1M"))
      (libsource (lib "Darkglass Electronics") (part "Resistor"))
    )
    (comp (ref "R39")
      (value "Res 10k 1% 0603")
      (footprint "0603-RES")
      (description "Resistor 10k +-1% 0603 Thick film 0.1W +- 100ppm/°C")
      (fields (field (name "RESISTANCE") "10k") (field (name "POWER") "100mW"))
      (libsource (lib "Darkglass Electronics") (part "Resistor"))
    )
    (comp (ref "R40")
      (value "Res 20k 1% 0603")
      (footprint "0603-RES")
      (description "Resistor 20k +-1% 0603 Thin film 0.1W +-50ppm/°C")
      (fields (field (name "RESISTANCE") "20k") (field (name "POWER") "100mW"))
      (libsource (lib "Darkglass Electronics") (part "Resistor"))
    )
    (comp (ref "R41")
      (value "Res 3.3k 1% 0603")
      (footprint "0603-RES")
      (description "Resistor 3.3k +-1% 0603 Thin film 0.1W +-50ppm/°C")
      (fields (field (name "POWER") "100mW") (field (name "RESISTANCE") "3.3k"))
      (libsource (lib "Darkglass Electronics") (part "Resistor"))
    )
    (comp (ref "R42")
      (value "Res 10k 1% 0603")
      (footprint "0603-RES")
      (description "Resistor 10k +-1% 0603 Thick film 0.1W +- 100ppm/°C")
      (fields (field (name "RESISTANCE") "10k") (field (name "POWER") "100mW"))
      (libsource (lib "Darkglass Electronics") (part "Resistor"))
    )
    (comp (ref "R43")
      (value "Res 10k 1% 0603")
      (footprint "0603-RES")
      (description "Resistor 10k +-1% 0603 Thick film 0.1W +- 100ppm/°C")
      (fields (field (name "RESISTANCE") "10k") (field (name "POWER") "100mW"))
      (libsource (lib "Darkglass Electronics") (part "Resistor"))
    )
    (comp (ref "R44")
      (value "Res 10k 1% 0603")
      (footprint "0603-RES")
      (description "Resistor 10k +-1% 0603 Thick film 0.1W +- 100ppm/°C")
      (fields (field (name "RESISTANCE") "10k") (field (name "POWER") "100mW"))
      (libsource (lib "Darkglass Electronics") (part "Resistor"))
    )
    (comp (ref "R45")
      (value "Res 100k 1% 0603")
      (footprint "0603-RES")
      (description "Resistor 100k +-1% 0603 Thin film 0.1W +-50ppm/°C")
      (fields (field (name "POWER") "100mW") (field (name "RESISTANCE") "100k"))
      (libsource (lib "Darkglass Electronics") (part "Resistor"))
    )
    (comp (ref "R46")
      (value "Res 1M 1% 0603")
      (footprint "0603-RES")
      (description "Resistor 1M +-1% 0603 Thin film 0.1W +-50ppm/°C")
      (fields (field (name "POWER") "100mW") (field (name "RESISTANCE") "1M"))
      (libsource (lib "Darkglass Electronics") (part "Resistor"))
    )
    (comp (ref "R47")
      (value "Res 100R 1% 0805")
      (footprint "0805-RES")
      (description "Resistor 100R +-1% 0805 Thin film 0.125W +-50ppm/°C")
      (fields (field (name "POWER") "125mW") (field (name "RESISTANCE") "100"))
      (libsource (lib "Darkglass Electronics") (part "Resistor"))
    )
    (comp (ref "R48")
      (value "Res 4.7k 1% 0603")
      (footprint "0603-RES")
      (description "Resistor 4.7k +-1% 0603 Thin film 0.1W +-50ppm/°C")
      (fields (field (name "RESISTANCE") "4.7k") (field (name "POWER") "100mW"))
      (libsource (lib "Darkglass Electronics") (part "Resistor"))
    )
    (comp (ref "R49")
      (value "Res 47k 1% 0603")
      (footprint "0603-RES")
      (description "Resistor 47k +-1% 0603 Thin film 0.1W +-50ppm/°C")
      (fields (field (name "RESISTANCE") "47k") (field (name "POWER") "100mW"))
      (libsource (lib "Darkglass Electronics") (part "Resistor"))
    )
    (comp (ref "R50")
      (value "Res 10k 1% 0603")
      (footprint "0603-RES")
      (description "Resistor 10k +-1% 0603 Thick film 0.1W +- 100ppm/°C")
      (fields (field (name "RESISTANCE") "10k") (field (name "POWER") "100mW"))
      (libsource (lib "Darkglass Electronics") (part "Resistor"))
    )
    (comp (ref "R51")
      (value "Res 6.81k 1% 0603")
      (footprint "0603-RES")
      (description "Resistor 6.81k +-1% 0603 Thin film 0.1W +-50ppm/°C")
      (fields (field (name "POWER") "100mW") (field (name "RESISTANCE") "6.81k"))
      (libsource (lib "Darkglass Electronics") (part "Resistor"))
    )
    (comp (ref "R52")
      (value "Res 10k 1% 0603")
      (footprint "0603-RES")
      (description "Resistor 10k +-1% 0603 Thick film 0.1W +- 100ppm/°C")
      (fields (field (name "RESISTANCE") "10k") (field (name "POWER") "100mW"))
      (libsource (lib "Darkglass Electronics") (part "Resistor"))
    )
    (comp (ref "R53")
      (value "Res 20k 1% 0603")
      (footprint "0603-RES")
      (description "Resistor 20k +-1% 0603 Thin film 0.1W +-50ppm/°C")
      (fields (field (name "RESISTANCE") "20k") (field (name "POWER") "100mW"))
      (libsource (lib "Darkglass Electronics") (part "Resistor"))
    )
    (comp (ref "R54")
      (value "Res 20k 1% 0603")
      (footprint "0603-RES")
      (description "Resistor 20k +-1% 0603 Thin film 0.1W +-50ppm/°C")
      (fields (field (name "RESISTANCE") "20k") (field (name "POWER") "100mW"))
      (libsource (lib "Darkglass Electronics") (part "Resistor"))
    )
    (comp (ref "R55")
      (value "Res 10k 1% 0603")
      (footprint "0603-RES")
      (description "Resistor 10k +-1% 0603 Thick film 0.1W +- 100ppm/°C")
      (fields (field (name "RESISTANCE") "10k") (field (name "POWER") "100mW"))
      (libsource (lib "Darkglass Electronics") (part "Resistor"))
    )
    (comp (ref "R56")
      (value "Res 100k 1% 0603")
      (footprint "0603-RES")
      (description "Resistor 100k +-1% 0603 Thin film 0.1W +-50ppm/°C")
      (fields (field (name "POWER") "100mW") (field (name "RESISTANCE") "100k"))
      (libsource (lib "Darkglass Electronics") (part "Resistor"))
    )
    (comp (ref "R57")
      (value "Res 100k 1% 0603")
      (footprint "0603-RES")
      (description "Resistor 100k +-1% 0603 Thin film 0.1W +-50ppm/°C")
      (fields (field (name "POWER") "100mW") (field (name "RESISTANCE") "100k"))
      (libsource (lib "Darkglass Electronics") (part "Resistor"))
    )
    (comp (ref "R58")
      (value "Res 100k 1% 0603")
      (footprint "0603-RES")
      (description "Resistor 100k +-1% 0603 Thin film 0.1W +-50ppm/°C")
      (fields (field (name "POWER") "100mW") (field (name "RESISTANCE") "100k"))
      (libsource (lib "Darkglass Electronics") (part "Resistor"))
    )
    (comp (ref "R59")
      (value "Res 2.2k 1% 0603")
      (footprint "0603-RES")
      (description "Resistor 2.2k +-1% 0603 Thin film 0.1W +-50ppm/°C")
      (fields (field (name "POWER") "100mW") (field (name "RESISTANCE") "2.2k"))
      (libsource (lib "Darkglass Electronics") (part "Resistor"))
    )
    (comp (ref "R60")
      (value "Res 1M 1% 0603")
      (footprint "0603-RES")
      (description "Resistor 1M +-1% 0603 Thin film 0.1W +-50ppm/°C")
      (fields (field (name "POWER") "100mW") (field (name "RESISTANCE") "1M"))
      (libsource (lib "Darkglass Electronics") (part "Resistor"))
    )
    (comp (ref "R61")
      (value "Res 4.7k 1% 0603")
      (footprint "0603-RES")
      (description "Resistor 4.7k +-1% 0603 Thin film 0.1W +-50ppm/°C")
      (fields (field (name "RESISTANCE") "4.7k") (field (name "POWER") "100mW"))
      (libsource (lib "Darkglass Electronics") (part "Resistor"))
    )
    (comp (ref "S1")
      (value "Tact footswitch, SPST")
      (footprint "Tact-SKHCBEA010")
      (description "Tactile Switches 12x12x4.3mm 130gf")
      (fields
        (field (name "MANUFACTURER PART NUMBER") "SKHCBFA010")
        (field (name "DARKGLASS PART") "D00-0022")
      )
      (libsource (lib "Darkglass Electronics") (part "Tact footswitch"))
    )
    (comp (ref "U1")
      (value "TL072CD")
      (footprint "SOIC8-127P600X175-8N")
      (description "Operational Amplifiers - Op Amps Dual Low Noise JFET SOIC8")
      (libsource (lib "Darkglass Electronics") (part "TL072CD"))
    )
    (comp (ref "U2")
      (value "TL072CD")
      (footprint "SOIC8-127P600X175-8N")
      (description "Operational Amplifiers - Op Amps Dual Low Noise JFET SOIC8")
      (libsource (lib "Darkglass Electronics") (part "TL072CD"))
    )
    (comp (ref "U4")
      (value "TL072CD")
      (footprint "SOIC8-127P600X175-8N")
      (description "Operational Amplifiers - Op Amps Dual Low Noise JFET SOIC8")
      (libsource (lib "Darkglass Electronics") (part "TL072CD"))
    )
    (comp (ref "U5")
      (value "TL072CD")
      (footprint "SOIC8-127P600X175-8N")
      (description "Operational Amplifiers - Op Amps Dual Low Noise JFET SOIC8")
      (libsource (lib "Darkglass Electronics") (part "TL072CD"))
    )
    (comp (ref "U6")
      (value "MC33179D")
      (footprint "SOIC14-127P600X175-14N")
      (description "Operational Amplifiers - Op Amps 2-18V Quad Low Power Industrial Temp SOIC14")
      (fields
        (field (name "MANUFACTURER PART NUMBER") "MC33179DR2G")
        (field (name "MANUFACTURER") "ON Semiconductor")
      )
      (libsource (lib "") (part "Symbol_4"))
    )
    (comp (ref "U7")
      (value "CD4013BME")
      (footprint "SOIC14-127P600X175-14N")
      (description "IC D-TYPE POS TRG DUAL 14SOIC")
      (fields
        (field (name "MANUFACTURER PART NUMBER") "CD4013BME4")
        (field (name "MANUFACTURER") "Texas Instruments")
      )
      (libsource (lib "Darkglass Electronics") (part "Symbol"))
    )
    (comp (ref "U8")
      (value "CD4013BME")
      (footprint "SOIC14-127P600X175-14N")
      (description "IC D-TYPE POS TRG DUAL 14SOIC")
      (fields
        (field (name "MANUFACTURER PART NUMBER") "CD4013BME4")
        (field (name "MANUFACTURER") "Texas Instruments")
      )
      (libsource (lib "Darkglass Electronics") (part "Symbol"))
    )
    (comp (ref "U9")
      (value "LM2611BMF/NOPB")
      (footprint "DBV0005A_M")
      (description "1.4MHz Cuk Converter, 5-pin SOT-23, Pb-Free")
      (fields (field (name "MANUFACTURER") "Texas Instruments"))
      (libsource (lib "Altium Content Vault") (part "PM-DCDC-LM2611"))
    )
    (comp (ref "V1")
      (value "Var AVRF101U6R8KT242")
      (footprint "0402 COMPONENT")
      (description "Varistor 0402 28VDC 6.8pF 10% Audio Line")
      (fields
        (field (name "MANUFACTURER") "TDK")
        (field (name "MANUFACTURER PART NUMBER") "AVRF101U6R8KT242")
        (field (name "SOURCE") "jimi.SchLib")
      )
      (libsource (lib "") (part "Symbol_5"))
    )
    (comp (ref "V2")
      (value "Var AVRF101U6R8KT242")
      (footprint "0402 COMPONENT")
      (description "Varistor 0402 28VDC 6.8pF 10% Audio Line")
      (fields
        (field (name "MANUFACTURER") "TDK")
        (field (name "MANUFACTURER PART NUMBER") "AVRF101U6R8KT242")
        (field (name "SOURCE") "jimi.SchLib")
      )
      (libsource (lib "") (part "Symbol_5"))
    )
    (comp (ref "VR1")
      (value "Pot100kA 9mm")
      (footprint "LJV 9mm pot")
      (description "LJV 9mm pot")
      (fields
        (field (name "DARKGLASS PART") "D00-0000")
        (field (name "MANUFACTURER PART NUMBER") "RP09110NOBA-H02-1484 (A104,KA15A6.5)")
      )
      (libsource (lib "Darkglass Electronics") (part "Pot100kA 9mm"))
    )
    (comp (ref "VR2")
      (value "Pot100kC 9mm D-Shaft")
      (footprint "LJV 9mm pot")
      (description "LJV 9mm pot")
      (fields (field (name "DARKGLASS PART") "D00-0002"))
      (libsource (lib "Darkglass Electronics") (part "Pot100kC 9mm"))
    )
    (comp (ref "VR3")
      (value "Pot100kA 9mm")
      (footprint "LJV 9mm pot")
      (description "LJV 9mm pot")
      (fields
        (field (name "MANUFACTURER PART NUMBER") "RP09110NOBA-H02-1484 (A104,KA15A6.5)")
        (field (name "DARKGLASS PART") "D00-0000")
      )
      (libsource (lib "Darkglass Electronics") (part "Pot100kA 9mm"))
    )
    (comp (ref "VR4")
      (value "Pot100kB 9mm D-shaft with switch")
      (footprint "LJV 9mm pot with switch")
      (description "LJV 9mm pot D-shaft with switch")
      (fields (field (name "MANUFACTURER") "LJV"))
      (libsource (lib "") (part "Symbol_6"))
    )
  )
  (nets
    (net (code "1") (name "+9V") (class "Default")
      (node (ref "C10") (pin "2") (pinfunction "2_2") (pintype "passive"))
      (node (ref "C11") (pin "2") (pinfunction "2_2") (pintype "passive"))
      (node (ref "C13") (pin "2") (pinfunction "2_2") (pintype "passive"))
      (node (ref "C20") (pin "1") (pinfunction "1_1") (pintype "passive"))
      (node (ref "C21") (pin "2") (pinfunction "2_2") (pintype "passive"))
      (node (ref "C38") (pin "1") (pinfunction "1_1") (pintype "passive"))
      (node (ref "C8") (pin "1") (pinfunction "1_1") (pintype "passive"))
      (node (ref "C9") (pin "2") (pinfunction "2_2") (pintype "passive"))
      (node (ref "D13") (pin "2") (pinfunction "K_2") (pintype "passive"))
      (node (ref "D3") (pin "2") (pinfunction "2_2") (pintype "passive"))
      (node (ref "L1") (pin "1") (pinfunction "1_1") (pintype "passive"))
      (node (ref "R18") (pin "2") (pinfunction "2_2") (pintype "passive"))
      (node (ref "R25") (pin "1") (pinfunction "1_1") (pintype "passive"))
      (node (ref "R4") (pin "2") (pinfunction "2_2") (pintype "passive"))
      (node (ref "U1") (pin "8") (pinfunction "V+_8") (pintype "power_in"))
      (node (ref "U2") (pin "8") (pinfunction "V+_8") (pintype "power_in"))
      (node (ref "U4") (pin "8") (pinfunction "V+_8") (pintype "power_in"))
      (node (ref "U5") (pin "8") (pinfunction "V+_8") (pintype "power_in"))
      (node (ref "U6") (pin "4") (pinfunction "4_4") (pintype "power_in"))
      (node (ref "U9") (pin "5") (pinfunction "VIN_5") (pintype "power_in"))
    )
    (net (code "2") (name "+9VD") (class "Default")
      (node (ref "C1") (pin "1") (pinfunction "1_1") (pintype "passive"))
      (node (ref "C14") (pin "1") (pinfunction "1_1") (pintype "passive"))
      (node (ref "C16") (pin "1") (pinfunction "1_1") (pintype "passive"))
      (node (ref "D1") (pin "2") (pinfunction "2_2") (pintype "passive"))
      (node (ref "R4") (pin "1") (pinfunction "1_1") (pintype "passive"))
      (node (ref "S1") (pin "1") (pinfunction "COMMON1_1") (pintype "passive"))
      (node (ref "S1") (pin "2") (pinfunction "COMMON2_2") (pintype "passive"))
      (node (ref "U7") (pin "14") (pinfunction "VDD_14") (pintype "passive"))
      (node (ref "U8") (pin "14") (pinfunction "VDD_14") (pintype "passive"))
      (node (ref "VR4") (pin "6") (pinfunction "SW1_6") (pintype "passive"))
    )
    (net (code "3") (name "-9V") (class "Default")
      (node (ref "C18") (pin "2") (pinfunction "2_2") (pintype "passive"))
      (node (ref "C2") (pin "1") (pinfunction "1_1") (pintype "passive"))
      (node (ref "C22") (pin "1") (pinfunction "1_1") (pintype "passive"))
      (node (ref "C27") (pin "2") (pinfunction "2_2") (pintype "passive"))
      (node (ref "C3") (pin "1") (pinfunction "1_1") (pintype "passive"))
      (node (ref "C4") (pin "1") (pinfunction "1_1") (pintype "passive"))
      (node (ref "C5") (pin "1") (pinfunction "1_1") (pintype "passive"))
      (node (ref "C7") (pin "1") (pinfunction "1_1") (pintype "passive"))
      (node (ref "D13") (pin "1") (pinfunction "A_1") (pintype "passive"))
      (node (ref "L2") (pin "2") (pinfunction "2_2") (pintype "passive"))
      (node (ref "R17") (pin "1") (pinfunction "1_1") (pintype "passive"))
      (node (ref "U1") (pin "4") (pinfunction "V-_4") (pintype "power_in"))
      (node (ref "U2") (pin "4") (pinfunction "V-_4") (pintype "power_in"))
      (node (ref "U4") (pin "4") (pinfunction "V-_4") (pintype "power_in"))
      (node (ref "U5") (pin "4") (pinfunction "V-_4") (pintype "power_in"))
      (node (ref "U6") (pin "11") (pinfunction "11_11") (pintype "power_in"))
    )
    (net (code "4") (name "/Blend") (class "Default")
      (node (ref "C39") (pin "2") (pinfunction "2_2") (pintype "passive"))
      (node (ref "Q4") (pin "1") (pinfunction "D_1") (pintype "passive"))
      (node (ref "R57") (pin "2") (pinfunction "2_2") (pintype "passive"))
    )
    (net (code "5") (name "/CV") (class "Default")
      (node (ref "OC1") (pin "A") (pinfunction "A_A") (pintype "passive"))
      (node (ref "R35") (pin "1") (pinfunction "1_1") (pintype "passive"))
    )
    (net (code "6") (name "/Clean") (class "Default")
      (node (ref "Q2") (pin "1") (pinfunction "D_1") (pintype "passive"))
      (node (ref "R45") (pin "2") (pinfunction "2_2") (pintype "passive"))
      (node (ref "U2") (pin "1") (pinfunction "OUT_1") (pintype "output"))
      (node (ref "U2") (pin "2") (pinfunction "IN-_2") (pintype "input"))
      (node (ref "U2") (pin "5") (pinfunction "IN+_5") (pintype "input"))
      (node (ref "VR1") (pin "1") (pinfunction "CCWPIN_1") (pintype "passive"))
    )
    (net (code "7") (name "/CompIn") (class "Default")
      (node (ref "C42") (pin "2") (pinfunction "2_2") (pintype "passive"))
      (node (ref "R60") (pin "1") (pinfunction "1_1") (pintype "passive"))
      (node (ref "U5") (pin "3") (pinfunction "IN+_3") (pintype "input"))
    )
    (net (code "8") (name "/CompOut") (class "Default")
      (node (ref "C40") (pin "2") (pinfunction "2_2") (pintype "passive"))
      (node (ref "R26") (pin "1") (pinfunction "1_1") (pintype "passive"))
      (node (ref "U1") (pin "3") (pinfunction "IN+_3") (pintype "input"))
      (node (ref "VR3") (pin "3") (pinfunction "CWPIN_3") (pintype "passive"))
    )
    (net (code "9") (name "/MB") (class "Default")
      (node (ref "Q3") (pin "1") (pinfunction "D_1") (pintype "passive"))
      (node (ref "R58") (pin "2") (pinfunction "2_2") (pintype "passive"))
      (node (ref "R61") (pin "2") (pinfunction "2_2") (pintype "passive"))
      (node (ref "U4") (pin "1") (pinfunction "OUT_1") (pintype "output"))
    )
    (net (code "10") (name "/ModeOff") (class "Default")
      (node (ref "R19") (pin "2") (pinfunction "2_2") (pintype "passive"))
      (node (ref "R24") (pin "1") (pinfunction "1_1") (pintype "passive"))
      (node (ref "U7") (pin "2") (pinfunction "NQ_2") (pintype "passive"))
      (node (ref "U7") (pin "5") (pinfunction "5_5") (pintype "passive"))
    )
    (net (code "11") (name "/ModeOn") (class "Default")
      (node (ref "R21") (pin "2") (pinfunction "2_2") (pintype "passive"))
      (node (ref "R27") (pin "1") (pinfunction "1_1") (pintype "passive"))
      (node (ref "U7") (pin "1") (pinfunction "Q_1") (pintype "power_in"))
    )
    (net (code "12") (name "/OutBuffer") (class "Default")
      (node (ref "C41") (pin "2") (pinfunction "2_2") (pintype "passive"))
      (node (ref "R30") (pin "1") (pinfunction "1_1") (pintype "passive"))
      (node (ref "U1") (pin "5") (pinfunction "IN+_5") (pintype "input"))
    )
    (net (code "13") (name "/PreOut") (class "Default")
      (node (ref "Q1") (pin "1") (pinfunction "D_1") (pintype "passive"))
      (node (ref "R48") (pin "1") (pinfunction "1_1") (pintype "passive"))
      (node (ref "R51") (pin "1") (pinfunction "1_1") (pintype "passive"))
      (node (ref "R56") (pin "2") (pinfunction "2_2") (pintype "passive"))
      (node (ref "U2") (pin "7") (pinfunction "7_7") (pintype "output"))
    )
    (net (code "14") (name "/TactOff") (class "Default")
      (node (ref "R28") (pin "1") (pinfunction "1_1") (pintype "passive"))
      (node (ref "U8") (pin "2") (pinfunction "NQ_2") (pintype "passive"))
      (node (ref "U8") (pin "5") (pinfunction "5_5") (pintype "passive"))
    )
    (net (code "15") (name "/TactOn") (class "Default")
      (node (ref "R20") (pin "2") (pinfunction "2_2") (pintype "passive"))
      (node (ref "R38") (pin "1") (pinfunction "1_1") (pintype "passive"))
      (node (ref "U8") (pin "1") (pinfunction "Q_1") (pintype "power_in"))
    )
    (net (code "16") (name "GND") (class "Default")
      (node (ref "C1") (pin "2") (pinfunction "2_2") (pintype "passive"))
      (node (ref "C10") (pin "1") (pinfunction "1_1") (pintype "passive"))
      (node (ref "C11") (pin "1") (pinfunction "1_1") (pintype "passive"))
      (node (ref "C13") (pin "1") (pinfunction "1_1") (pintype "passive"))
      (node (ref "C15") (pin "2") (pinfunction "2_2") (pintype "passive"))
      (node (ref "C17") (pin "2") (pinfunction "2_2") (pintype "passive"))
      (node (ref "C18") (pin "1") (pinfunction "1_1") (pintype "passive"))
      (node (ref "C2") (pin "2") (pinfunction "2_2") (pintype "passive"))
      (node (ref "C20") (pin "2") (pinfunction "2_2") (pintype "passive"))
      (node (ref "C21") (pin "1") (pinfunction "1_1") (pintype "passive"))
      (node (ref "C26") (pin "2") (pinfunction "2_2") (pintype "passive"))
      (node (ref "C29") (pin "1") (pinfunction "1_1") (pintype "passive"))
      (node (ref "C3") (pin "2") (pinfunction "2_2") (pintype "passive"))
      (node (ref "C30") (pin "2") (pinfunction "2_2") (pintype "passive"))
      (node (ref "C31") (pin "2") (pinfunction "2_2") (pintype "passive"))
      (node (ref "C32") (pin "1") (pinfunction "1_1") (pintype "passive"))
      (node (ref "C33") (pin "2") (pinfunction "2_2") (pintype "passive"))
      (node (ref "C35") (pin "2") (pinfunction "2_2") (pintype "passive"))
      (node (ref "C36") (pin "2") (pinfunction "2_2") (pintype "passive"))
      (node (ref "C37") (pin "2") (pinfunction "2_2") (pintype "passive"))
      (node (ref "C38") (pin "2") (pinfunction "2_2") (pintype "passive"))
      (node (ref "C4") (pin "2") (pinfunction "2_2") (pintype "passive"))
      (node (ref "C5") (pin "2") (pinfunction "2_2") (pintype "passive"))
      (node (ref "C7") (pin "2") (pinfunction "2_2") (pintype "passive"))
      (node (ref "C8") (pin "2") (pinfunction "2_2") (pintype "passive"))
      (node (ref "C9") (pin "1") (pinfunction "1_1") (pintype "passive"))
      (node (ref "D1") (pin "1") (pinfunction "1_1") (pintype "passive"))
      (node (ref "D2") (pin "2") (pinfunction "K_2") (pintype "passive"))
      (node (ref "D3") (pin "1") (pinfunction "1_1") (pintype "passive"))
      (node (ref "D5") (pin "2") (pinfunction "2_2") (pintype "passive"))
      (node (ref "J1") (pin "1") (pinfunction "1_1") (pintype "power_in"))
      (node (ref "J2") (pin "1") (pinfunction "1_1") (pintype "passive"))
      (node (ref "J2") (pin "2") (pinfunction "2_2") (pintype "passive"))
      (node (ref "J2") (pin "4") (pinfunction "4_4") (pintype "passive"))
      (node (ref "J2") (pin "5") (pinfunction "5_5") (pintype "passive"))
      (node (ref "J2") (pin "6") (pinfunction "6_6") (pintype "passive"))
      (node (ref "J3") (pin "1") (pinfunction "1_1") (pintype "passive"))
      (node (ref "J3") (pin "2") (pinfunction "2_2") (pintype "passive"))
      (node (ref "J3") (pin "5") (pinfunction "5_5") (pintype "passive"))
      (node (ref "J3") (pin "6") (pinfunction "6_6") (pintype "passive"))
      (node (ref "LED1") (pin "2") (pinfunction "K_2") (pintype "passive"))
      (node (ref "OC1") (pin "K") (pinfunction "C_K") (pintype "passive"))
      (node (ref "R1") (pin "1") (pinfunction "1_1") (pintype "passive"))
      (node (ref "R11") (pin "2") (pinfunction "2_2") (pintype "passive"))
      (node (ref "R13") (pin "2") (pinfunction "2_2") (pintype "passive"))
      (node (ref "R15") (pin "2") (pinfunction "2_2") (pintype "passive"))
      (node (ref "R2") (pin "1") (pinfunction "1_1") (pintype "passive"))
      (node (ref "R22") (pin "2") (pinfunction "2_2") (pintype "passive"))
      (node (ref "R26") (pin "2") (pinfunction "2_2") (pintype "passive"))
      (node (ref "R29") (pin "1") (pinfunction "1_1") (pintype "passive"))
      (node (ref "R30") (pin "2") (pinfunction "2_2") (pintype "passive"))
      (node (ref "R32") (pin "1") (pinfunction "1_1") (pintype "passive"))
      (node (ref "R37") (pin "1") (pinfunction "1_1") (pintype "passive"))
      (node (ref "R46") (pin "2") (pinfunction "2_2") (pintype "passive"))
      (node (ref "R50") (pin "1") (pinfunction "1_1") (pintype "passive"))
      (node (ref "R52") (pin "1") (pinfunction "1_1") (pintype "passive"))
      (node (ref "R55") (pin "1") (pinfunction "1_1") (pintype "passive"))
      (node (ref "R59") (pin "1") (pinfunction "1_1") (pintype "passive"))
      (node (ref "R60") (pin "2") (pinfunction "2_2") (pintype "passive"))
      (node (ref "R8") (pin "1") (pinfunction "1_1") (pintype "passive"))
      (node (ref "R9") (pin "1") (pinfunction "1_1") (pintype "passive"))
      (node (ref "U4") (pin "5") (pinfunction "IN+_5") (pintype "input"))
      (node (ref "U6") (pin "10") (pinfunction "10_10") (pintype "input"))
      (node (ref "U6") (pin "5") (pinfunction "5_5") (pintype "input"))
      (node (ref "U7") (pin "11") (pinfunction "CK_11") (pintype "passive"))
      (node (ref "U7") (pin "6") (pinfunction "S_6") (pintype "passive"))
      (node (ref "U7") (pin "7") (pinfunction "VSS_7") (pintype "passive"))
      (node (ref "U7") (pin "9") (pinfunction "D_9") (pintype "passive"))
      (node (ref "U8") (pin "11") (pinfunction "CK_11") (pintype "passive"))
      (node (ref "U8") (pin "6") (pinfunction "S_6") (pintype "passive"))
      (node (ref "U8") (pin "7") (pinfunction "VSS_7") (pintype "passive"))
      (node (ref "U8") (pin "9") (pinfunction "D_9") (pintype "passive"))
      (node (ref "U9") (pin "2") (pinfunction "GND_2") (pintype "power_in"))
      (node (ref "V1") (pin "1") (pinfunction "1_1") (pintype "passive"))
      (node (ref "V2") (pin "1") (pinfunction "1_1") (pintype "passive"))
      (node (ref "VR1") (pin "4") (pinfunction "4_4") (pintype "passive"))
      (node (ref "VR1") (pin "5") (pinfunction "5_5") (pintype "passive"))
      (node (ref "VR2") (pin "4") (pinfunction "4_4") (pintype "passive"))
      (node (ref "VR2") (pin "5") (pinfunction "5_5") (pintype "passive"))
      (node (ref "VR3") (pin "1") (pinfunction "CCWPIN_1") (pintype "passive"))
      (node (ref "VR3") (pin "4") (pinfunction "4_4") (pintype "passive"))
      (node (ref "VR3") (pin "5") (pinfunction "5_5") (pintype "passive"))
      (node (ref "VR4") (pin "4") (pinfunction "4_4") (pintype "passive"))
      (node (ref "VR4") (pin "5") (pinfunction "5_5") (pintype "passive"))
    )
    (net (code "17") (name "Net-(C14-Pad2)") (class "Default")
      (node (ref "C14") (pin "2") (pinfunction "2_2") (pintype "passive"))
      (node (ref "R1") (pin "2") (pinfunction "2_2") (pintype "passive"))
      (node (ref "R3") (pin "2") (pinfunction "2_2") (pintype "passive"))
    )
    (net (code "18") (name "Net-(C15-Pad1)") (class "Default")
      (node (ref "C15") (pin "1") (pinfunction "1_1") (pintype "passive"))
      (node (ref "R10") (pin "1") (pinfunction "1_1") (pintype "passive"))
      (node (ref "R6") (pin "1") (pinfunction "1_1") (pintype "passive"))
    )
    (net (code "19") (name "Net-(C16-Pad2)") (class "Default")
      (node (ref "C16") (pin "2") (pinfunction "2_2") (pintype "passive"))
      (node (ref "R2") (pin "2") (pinfunction "2_2") (pintype "passive"))
      (node (ref "R5") (pin "2") (pinfunction "2_2") (pintype "passive"))
    )
    (net (code "20") (name "Net-(C17-Pad1)") (class "Default")
      (node (ref "C17") (pin "1") (pinfunction "1_1") (pintype "passive"))
      (node (ref "R12") (pin "1") (pinfunction "1_1") (pintype "passive"))
      (node (ref "R7") (pin "1") (pinfunction "1_1") (pintype "passive"))
    )
    (net (code "21") (name "Net-(C19-Pad2)") (class "Default")
      (node (ref "C19") (pin "2") (pinfunction "2_2") (pintype "passive"))
      (node (ref "R22") (pin "1") (pinfunction "1_1") (pintype "passive"))
      (node (ref "R23") (pin "1") (pinfunction "1_1") (pintype "passive"))
    )
    (net (code "22") (name "Net-(C23-Pad2)") (class "Default")
      (node (ref "C23") (pin "2") (pinfunction "2_2") (pintype "passive"))
      (node (ref "R14") (pin "2") (pinfunction "2_2") (pintype "passive"))
      (node (ref "R8") (pin "2") (pinfunction "2_2") (pintype "passive"))
    )
    (net (code "23") (name "Net-(C24-Pad2)") (class "Default")
      (node (ref "C24") (pin "2") (pinfunction "2_2") (pintype "passive"))
      (node (ref "R16") (pin "2") (pinfunction "2_2") (pintype "passive"))
      (node (ref "R9") (pin "2") (pinfunction "2_2") (pintype "passive"))
    )
    (net (code "24") (name "Net-(C28-Pad1)") (class "Default")
      (node (ref "C28") (pin "1") (pinfunction "1_1") (pintype "passive"))
      (node (ref "R47") (pin "2") (pinfunction "2_2") (pintype "passive"))
    )
    (net (code "25") (name "Net-(C31-Pad1)") (class "Default")
      (node (ref "C31") (pin "1") (pinfunction "1_1") (pintype "passive"))
      (node (ref "R29") (pin "2") (pinfunction "2_2") (pintype "passive"))
      (node (ref "R31") (pin "2") (pinfunction "2_2") (pintype "passive"))
      (node (ref "U6") (pin "12") (pinfunction "12_12") (pintype "input"))
    )
    (net (code "26") (name "Net-(C33-Pad1)") (class "Default")
      (node (ref "C33") (pin "1") (pinfunction "1_1") (pintype "passive"))
      (node (ref "R36") (pin "2") (pinfunction "2_2") (pintype "passive"))
      (node (ref "U6") (pin "3") (pinfunction "3_3") (pintype "input"))
    )
    (net (code "27") (name "Net-(C40-Pad1)") (class "Default")
      (node (ref "C40") (pin "1") (pinfunction "1_1") (pintype "passive"))
      (node (ref "R53") (pin "2") (pinfunction "2_2") (pintype "passive"))
      (node (ref "U5") (pin "7") (pinfunction "7_7") (pintype "output"))
    )
    (net (code "28") (name "Net-(D2-A)") (class "Default")
      (node (ref "C25") (pin "2") (pinfunction "2_2") (pintype "passive"))
      (node (ref "D2") (pin "1") (pinfunction "A_1") (pintype "passive"))
      (node (ref "L2") (pin "1") (pinfunction "1_1") (pintype "passive"))
    )
    (net (code "29") (name "Net-(D4-PadA)") (class "Default")
      (node (ref "D4") (pin "A") (pinfunction "A_A") (pintype "passive"))
      (node (ref "J1") (pin "2") (pinfunction "2_2") (pintype "power_in"))
    )
    (net (code "30") (name "Net-(D4-PadK)") (class "Default")
      (node (ref "D4") (pin "K") (pinfunction "K_K") (pintype "passive"))
      (node (ref "L3") (pin "1") (pinfunction "1_1") (pintype "passive"))
    )
    (net (code "31") (name "Net-(D5-Pad1)") (class "Default")
      (node (ref "D5") (pin "1") (pinfunction "1_1") (pintype "passive"))
      (node (ref "R21") (pin "1") (pinfunction "1_1") (pintype "passive"))
    )
    (net (code "32") (name "Net-(D5-Pad3)") (class "Default")
      (node (ref "D5") (pin "3") (pinfunction "3_3") (pintype "passive"))
      (node (ref "R19") (pin "1") (pinfunction "1_1") (pintype "passive"))
    )
    (net (code "33") (name "Net-(D6-A)") (class "Default")
      (node (ref "D6") (pin "1") (pinfunction "A_1") (pintype "passive"))
      (node (ref "Q1") (pin "3") (pinfunction "G_3") (pintype "passive"))
      (node (ref "R56") (pin "1") (pinfunction "1_1") (pintype "passive"))
    )
    (net (code "34") (name "Net-(D6-K)") (class "Default")
      (node (ref "C26") (pin "1") (pinfunction "1_1") (pintype "passive"))
      (node (ref "D6") (pin "2") (pinfunction "K_2") (pintype "passive"))
      (node (ref "R24") (pin "2") (pinfunction "2_2") (pintype "passive"))
    )
    (net (code "35") (name "Net-(D7-A)") (class "Default")
      (node (ref "D7") (pin "1") (pinfunction "A_1") (pintype "passive"))
      (node (ref "Q2") (pin "3") (pinfunction "G_3") (pintype "passive"))
      (node (ref "R45") (pin "1") (pinfunction "1_1") (pintype "passive"))
    )
    (net (code "36") (name "Net-(D7-K)") (class "Default")
      (node (ref "C30") (pin "1") (pinfunction "1_1") (pintype "passive"))
      (node (ref "D7") (pin "2") (pinfunction "K_2") (pintype "passive"))
      (node (ref "R28") (pin "2") (pinfunction "2_2") (pintype "passive"))
    )
    (net (code "37") (name "Net-(D8-A)") (class "Default")
      (node (ref "D8") (pin "1") (pinfunction "A_1") (pintype "passive"))
      (node (ref "Q3") (pin "3") (pinfunction "G_3") (pintype "passive"))
      (node (ref "R58") (pin "1") (pinfunction "1_1") (pintype "passive"))
    )
    (net (code "38") (name "Net-(D8-K)") (class "Default")
      (node (ref "C29") (pin "2") (pinfunction "2_2") (pintype "passive"))
      (node (ref "D8") (pin "2") (pinfunction "K_2") (pintype "passive"))
      (node (ref "R27") (pin "2") (pinfunction "2_2") (pintype "passive"))
    )
    (net (code "39") (name "Net-(D9-A)") (class "Default")
      (node (ref "D9") (pin "1") (pinfunction "A_1") (pintype "passive"))
      (node (ref "Q4") (pin "3") (pinfunction "G_3") (pintype "passive"))
      (node (ref "R57") (pin "1") (pinfunction "1_1") (pintype "passive"))
    )
    (net (code "40") (name "Net-(D9-K)") (class "Default")
      (node (ref "C32") (pin "2") (pinfunction "2_2") (pintype "passive"))
      (node (ref "D9") (pin "2") (pinfunction "K_2") (pintype "passive"))
      (node (ref "R38") (pin "2") (pinfunction "2_2") (pintype "passive"))
    )
    (net (code "41") (name "Net-(D11-A)") (class "Default")
      (node (ref "D11") (pin "1") (pinfunction "A_1") (pintype "passive"))
      (node (ref "R39") (pin "1") (pinfunction "1_1") (pintype "passive"))
      (node (ref "R44") (pin "2") (pinfunction "2_2") (pintype "passive"))
    )
    (net (code "42") (name "Net-(D11-K)") (class "Default")
      (node (ref "D11") (pin "2") (pinfunction "K_2") (pintype "passive"))
      (node (ref "D12") (pin "1") (pinfunction "A_1") (pintype "passive"))
      (node (ref "U6") (pin "7") (pinfunction "7_7") (pintype "output"))
    )
    (net (code "43") (name "Net-(D12-K)") (class "Default")
      (node (ref "D12") (pin "2") (pinfunction "K_2") (pintype "passive"))
      (node (ref "R43") (pin "2") (pinfunction "2_2") (pintype "passive"))
      (node (ref "R44") (pin "1") (pinfunction "1_1") (pintype "passive"))
      (node (ref "U6") (pin "6") (pinfunction "6_6") (pintype "input"))
    )
    (net (code "44") (name "Net-(D13-K{slash}A)") (class "Default")
      (node (ref "C28") (pin "2") (pinfunction "2_2") (pintype "passive"))
      (node (ref "C36") (pin "1") (pinfunction "1_1") (pintype "passive"))
      (node (ref "D13") (pin "3") (pinfunction "K/A_3") (pintype "passive"))
      (node (ref "R46") (pin "1") (pinfunction "1_1") (pintype "passive"))
      (node (ref "U2") (pin "3") (pinfunction "IN+_3") (pintype "input"))
    )
    (net (code "45") (name "Net-(J2-Pad3)") (class "Default")
      (node (ref "J2") (pin "3") (pinfunction "3_3") (pintype "passive"))
      (node (ref "R23") (pin "2") (pinfunction "2_2") (pintype "passive"))
      (node (ref "V1") (pin "2") (pinfunction "2_2") (pintype "passive"))
    )
    (net (code "46") (name "Net-(J3-Pad3)") (class "Default")
      (node (ref "J3") (pin "3") (pinfunction "3_3") (pintype "passive"))
      (node (ref "J3") (pin "4") (pinfunction "4_4") (pintype "passive"))
      (node (ref "L4") (pin "1") (pinfunction "1_1") (pintype "passive"))
      (node (ref "V2") (pin "2") (pinfunction "2_2") (pintype "passive"))
    )
    (net (code "47") (name "Net-(L3-Pad2)") (class "Default")
      (node (ref "L3") (pin "2") (pinfunction "2_2") (pintype "passive"))
      (node (ref "R18") (pin "1") (pinfunction "1_1") (pintype "passive"))
    )
    (net (code "48") (name "Net-(L4-Pad2)") (class "Default")
      (node (ref "L4") (pin "2") (pinfunction "2_2") (pintype "passive"))
      (node (ref "R47") (pin "1") (pinfunction "1_1") (pintype "passive"))
    )
    (net (code "49") (name "Net-(LED1-A)") (class "Default")
      (node (ref "LED1") (pin "1") (pinfunction "A_1") (pintype "passive"))
      (node (ref "R20") (pin "1") (pinfunction "1_1") (pintype "passive"))
    )
    (net (code "50") (name "Net-(OC1-PC1)") (class "Default")
      (node (ref "OC1") (pin "C1") (pinfunction "PC1_C1") (pintype "passive"))
      (node (ref "R49") (pin "2") (pinfunction "2_2") (pintype "passive"))
      (node (ref "U5") (pin "5") (pinfunction "IN+_5") (pintype "input"))
    )
    (net (code "51") (name "Net-(OC1-PC2)") (class "Default")
      (node (ref "OC1") (pin "C2") (pinfunction "PC2_C2") (pintype "passive"))
      (node (ref "R59") (pin "2") (pinfunction "2_2") (pintype "passive"))
    )
    (net (code "52") (name "Net-(Q1-S)") (class "Default")
      (node (ref "C42") (pin "1") (pinfunction "1_1") (pintype "passive"))
      (node (ref "Q1") (pin "2") (pinfunction "S_2") (pintype "passive"))
      (node (ref "Q3") (pin "2") (pinfunction "S_2") (pintype "passive"))
    )
    (net (code "53") (name "Net-(Q2-S)") (class "Default")
      (node (ref "C41") (pin "1") (pinfunction "1_1") (pintype "passive"))
      (node (ref "Q2") (pin "2") (pinfunction "S_2") (pintype "passive"))
      (node (ref "Q4") (pin "2") (pinfunction "S_2") (pintype "passive"))
    )
    (net (code "54") (name "Net-(R31-Pad1)") (class "Default")
      (node (ref "R31") (pin "1") (pinfunction "1_1") (pintype "passive"))
      (node (ref "R40") (pin "2") (pinfunction "2_2") (pintype "passive"))
      (node (ref "U6") (pin "8") (pinfunction "8_8") (pintype "output"))
    )
    (net (code "55") (name "Net-(R32-Pad2)") (class "Default")
      (node (ref "R32") (pin "2") (pinfunction "2_2") (pintype "passive"))
      (node (ref "R33") (pin "1") (pinfunction "1_1") (pintype "passive"))
      (node (ref "U6") (pin "2") (pinfunction "2_2") (pintype "input"))
    )
    (net (code "56") (name "Net-(R33-Pad2)") (class "Default")
      (node (ref "R33") (pin "2") (pinfunction "2_2") (pintype "passive"))
      (node (ref "R34") (pin "1") (pinfunction "1_1") (pintype "passive"))
      (node (ref "R43") (pin "1") (pinfunction "1_1") (pintype "passive"))
      (node (ref "U6") (pin "1") (pinfunction "1_1") (pintype "output"))
    )
    (net (code "57") (name "Net-(R34-Pad2)") (class "Default")
      (node (ref "R34") (pin "2") (pinfunction "2_2") (pintype "passive"))
      (node (ref "R39") (pin "2") (pinfunction "2_2") (pintype "passive"))
      (node (ref "R40") (pin "1") (pinfunction "1_1") (pintype "passive"))
      (node (ref "U6") (pin "9") (pinfunction "9_9") (pintype "input"))
    )
    (net (code "58") (name "Net-(R35-Pad2)") (class "Default")
      (node (ref "R35") (pin "2") (pinfunction "2_2") (pintype "passive"))
      (node (ref "R54") (pin "2") (pinfunction "2_2") (pintype "passive"))
      (node (ref "U6") (pin "14") (pinfunction "14_14") (pintype "output"))
    )
    (net (code "59") (name "Net-(R37-Pad2)") (class "Default")
      (node (ref "R37") (pin "2") (pinfunction "2_2") (pintype "passive"))
      (node (ref "R54") (pin "1") (pinfunction "1_1") (pintype "passive"))
      (node (ref "U6") (pin "13") (pinfunction "13_13") (pintype "input"))
    )
    (net (code "60") (name "Net-(S1-NO1)") (class "Default")
      (node (ref "C24") (pin "1") (pinfunction "1_1") (pintype "passive"))
      (node (ref "R15") (pin "1") (pinfunction "1_1") (pintype "passive"))
      (node (ref "S1") (pin "3") (pinfunction "NO1_3") (pintype "passive"))
      (node (ref "S1") (pin "4") (pinfunction "NO2_4") (pintype "passive"))
    )
    (net (code "61") (name "Net-(U1A-IN-)") (class "Default")
      (node (ref "C34") (pin "1") (pinfunction "1_1") (pintype "passive"))
      (node (ref "R41") (pin "2") (pinfunction "2_2") (pintype "passive"))
      (node (ref "R42") (pin "1") (pinfunction "1_1") (pintype "passive"))
      (node (ref "U1") (pin "2") (pinfunction "IN-_2") (pintype "input"))
    )
    (net (code "62") (name "Net-(U1A-OUT)") (class "Default")
      (node (ref "C34") (pin "2") (pinfunction "2_2") (pintype "passive"))
      (node (ref "R42") (pin "2") (pinfunction "2_2") (pintype "passive"))
      (node (ref "U1") (pin "1") (pinfunction "OUT_1") (pintype "output"))
      (node (ref "VR1") (pin "3") (pinfunction "CWPIN_3") (pintype "passive"))
    )
    (net (code "63") (name "Net-(U1B-IN-)") (class "Default")
      (node (ref "C19") (pin "1") (pinfunction "1_1") (pintype "passive"))
      (node (ref "U1") (pin "6") (pinfunction "IN-_6") (pintype "input"))
      (node (ref "U1") (pin "7") (pinfunction "7_7") (pintype "output"))
    )
    (net (code "64") (name "Net-(U2B-IN-)") (class "Default")
      (node (ref "R50") (pin "2") (pinfunction "2_2") (pintype "passive"))
      (node (ref "R51") (pin "2") (pinfunction "2_2") (pintype "passive"))
      (node (ref "U2") (pin "6") (pinfunction "IN-_6") (pintype "input"))
    )
    (net (code "65") (name "Net-(U4A-IN+)") (class "Default")
      (node (ref "C37") (pin "1") (pinfunction "1_1") (pintype "passive"))
      (node (ref "U4") (pin "3") (pinfunction "IN+_3") (pintype "input"))
      (node (ref "VR4") (pin "2") (pinfunction "WIPER_2") (pintype "passive"))
      (node (ref "VR4") (pin "3") (pinfunction "CWPIN_3") (pintype "passive"))
    )
    (net (code "66") (name "Net-(U4A-IN-)") (class "Default")
      (node (ref "R55") (pin "2") (pinfunction "2_2") (pintype "passive"))
      (node (ref "R61") (pin "1") (pinfunction "1_1") (pintype "passive"))
      (node (ref "U4") (pin "2") (pinfunction "IN-_2") (pintype "input"))
    )
    (net (code "67") (name "Net-(U4B-IN-)") (class "Default")
      (node (ref "U4") (pin "6") (pinfunction "IN-_6") (pintype "input"))
      (node (ref "U4") (pin "7") (pinfunction "7_7") (pintype "output"))
    )
    (net (code "68") (name "Net-(U5A-IN-)") (class "Default")
      (node (ref "R49") (pin "1") (pinfunction "1_1") (pintype "passive"))
      (node (ref "U5") (pin "1") (pinfunction "OUT_1") (pintype "output"))
      (node (ref "U5") (pin "2") (pinfunction "IN-_2") (pintype "input"))
    )
    (net (code "69") (name "Net-(U5B-IN-)") (class "Default")
      (node (ref "R52") (pin "2") (pinfunction "2_2") (pintype "passive"))
      (node (ref "R53") (pin "1") (pinfunction "1_1") (pintype "passive"))
      (node (ref "U5") (pin "6") (pinfunction "IN-_6") (pintype "input"))
    )
    (net (code "70") (name "Net-(U7A-CK)") (class "Default")
      (node (ref "R6") (pin "2") (pinfunction "2_2") (pintype "passive"))
      (node (ref "U7") (pin "13") (pinfunction "Q_13") (pintype "passive"))
      (node (ref "U7") (pin "3") (pinfunction "CK_3") (pintype "passive"))
    )
    (net (code "71") (name "Net-(U7A-R)") (class "Default")
      (node (ref "R3") (pin "1") (pinfunction "1_1") (pintype "passive"))
      (node (ref "U7") (pin "4") (pinfunction "R_4") (pintype "passive"))
    )
    (net (code "72") (name "Net-(U7B-R)") (class "Default")
      (node (ref "R10") (pin "2") (pinfunction "2_2") (pintype "passive"))
      (node (ref "U7") (pin "10") (pinfunction "R_10") (pintype "passive"))
    )
    (net (code "73") (name "Net-(U7B-S)") (class "Default")
      (node (ref "R14") (pin "1") (pinfunction "1_1") (pintype "passive"))
      (node (ref "U7") (pin "8") (pinfunction "S_8") (pintype "passive"))
    )
    (net (code "74") (name "Net-(U8A-CK)") (class "Default")
      (node (ref "R7") (pin "2") (pinfunction "2_2") (pintype "passive"))
      (node (ref "U8") (pin "13") (pinfunction "Q_13") (pintype "passive"))
      (node (ref "U8") (pin "3") (pinfunction "CK_3") (pintype "passive"))
    )
    (net (code "75") (name "Net-(U8A-R)") (class "Default")
      (node (ref "R5") (pin "1") (pinfunction "1_1") (pintype "passive"))
      (node (ref "U8") (pin "4") (pinfunction "R_4") (pintype "passive"))
    )
    (net (code "76") (name "Net-(U8B-R)") (class "Default")
      (node (ref "R12") (pin "2") (pinfunction "2_2") (pintype "passive"))
      (node (ref "U8") (pin "10") (pinfunction "R_10") (pintype "passive"))
    )
    (net (code "77") (name "Net-(U8B-S)") (class "Default")
      (node (ref "R16") (pin "1") (pinfunction "1_1") (pintype "passive"))
      (node (ref "U8") (pin "8") (pinfunction "S_8") (pintype "passive"))
    )
    (net (code "78") (name "Net-(U9-NFB)") (class "Default")
      (node (ref "C22") (pin "2") (pinfunction "2_2") (pintype "passive"))
      (node (ref "R11") (pin "1") (pinfunction "1_1") (pintype "passive"))
      (node (ref "R17") (pin "2") (pinfunction "2_2") (pintype "passive"))
      (node (ref "U9") (pin "3") (pinfunction "NFB_3") (pintype "input"))
    )
    (net (code "79") (name "Net-(U9-SW)") (class "Default")
      (node (ref "C25") (pin "1") (pinfunction "1_1") (pintype "passive"))
      (node (ref "L1") (pin "2") (pinfunction "2_2") (pintype "passive"))
      (node (ref "U9") (pin "1") (pinfunction "SW_1") (pintype "power_in"))
    )
    (net (code "80") (name "Net-(U9-~{SHDN})") (class "Default")
      (node (ref "C27") (pin "1") (pinfunction "1_1") (pintype "passive"))
      (node (ref "R25") (pin "2") (pinfunction "2_2") (pintype "passive"))
      (node (ref "U9") (pin "4") (pinfunction "~{SHDN}_4") (pintype "input"))
    )
    (net (code "81") (name "Net-(VR1A-WIPER)") (class "Default")
      (node (ref "C39") (pin "1") (pinfunction "1_1") (pintype "passive"))
      (node (ref "VR1") (pin "2") (pinfunction "WIPER_2") (pintype "passive"))
    )
    (net (code "82") (name "Net-(VR2A-CCWPIN)") (class "Default")
      (node (ref "C35") (pin "1") (pinfunction "1_1") (pintype "passive"))
      (node (ref "VR2") (pin "1") (pinfunction "CCWPIN_1") (pintype "passive"))
      (node (ref "VR2") (pin "2") (pinfunction "WIPER_2") (pintype "passive"))
    )
    (net (code "83") (name "Net-(VR2A-CWPIN)") (class "Default")
      (node (ref "R41") (pin "1") (pinfunction "1_1") (pintype "passive"))
      (node (ref "VR2") (pin "3") (pinfunction "CWPIN_3") (pintype "passive"))
    )
    (net (code "84") (name "Net-(VR3A-WIPER)") (class "Default")
      (node (ref "R36") (pin "1") (pinfunction "1_1") (pintype "passive"))
      (node (ref "VR3") (pin "2") (pinfunction "WIPER_2") (pintype "passive"))
    )
    (net (code "85") (name "Net-(VR4A-CCWPIN)") (class "Default")
      (node (ref "R48") (pin "2") (pinfunction "2_2") (pintype "passive"))
      (node (ref "VR4") (pin "1") (pinfunction "CCWPIN_1") (pintype "passive"))
    )
    (net (code "86") (name "Net-(VR4C-SW2)") (class "Default")
      (node (ref "C23") (pin "1") (pinfunction "1_1") (pintype "passive"))
      (node (ref "R13") (pin "1") (pinfunction "1_1") (pintype "passive"))
      (node (ref "VR4") (pin "7") (pinfunction "SW2_7") (pintype "passive"))
    )
    (net (code "87") (name "unconnected-(J1-Pad3)") (class "Default")
      (node (ref "J1") (pin "3") (pinfunction "3_3") (pintype "power_in"))
    )
    (net (code "88") (name "unconnected-(J2-Pad7)") (class "Default")
      (node (ref "J2") (pin "7") (pinfunction "7_7") (pintype "passive"))
    )
    (net (code "89") (name "unconnected-(J2-Pad8)") (class "Default")
      (node (ref "J2") (pin "8") (pinfunction "8_8") (pintype "passive"))
    )
    (net (code "90") (name "unconnected-(J3-Pad7)") (class "Default")
      (node (ref "J3") (pin "7") (pinfunction "7_7") (pintype "passive"))
    )
    (net (code "91") (name "unconnected-(J3-Pad8)") (class "Default")
      (node (ref "J3") (pin "8") (pinfunction "8_8") (pintype "passive"))
    )
    (net (code "92") (name "unconnected-(U7B-NQ-Pad12)") (class "Default")
      (node (ref "U7") (pin "12") (pinfunction "NQ_12") (pintype "passive"))
    )
    (net (code "93") (name "unconnected-(U8B-NQ-Pad12)") (class "Default")
      (node (ref "U8") (pin "12") (pinfunction "NQ_12") (pintype "passive"))
    )
  )
)
